# mcat-4cu-b-v2b.net
KiCad netlist of a schematic drawn in EAGLE
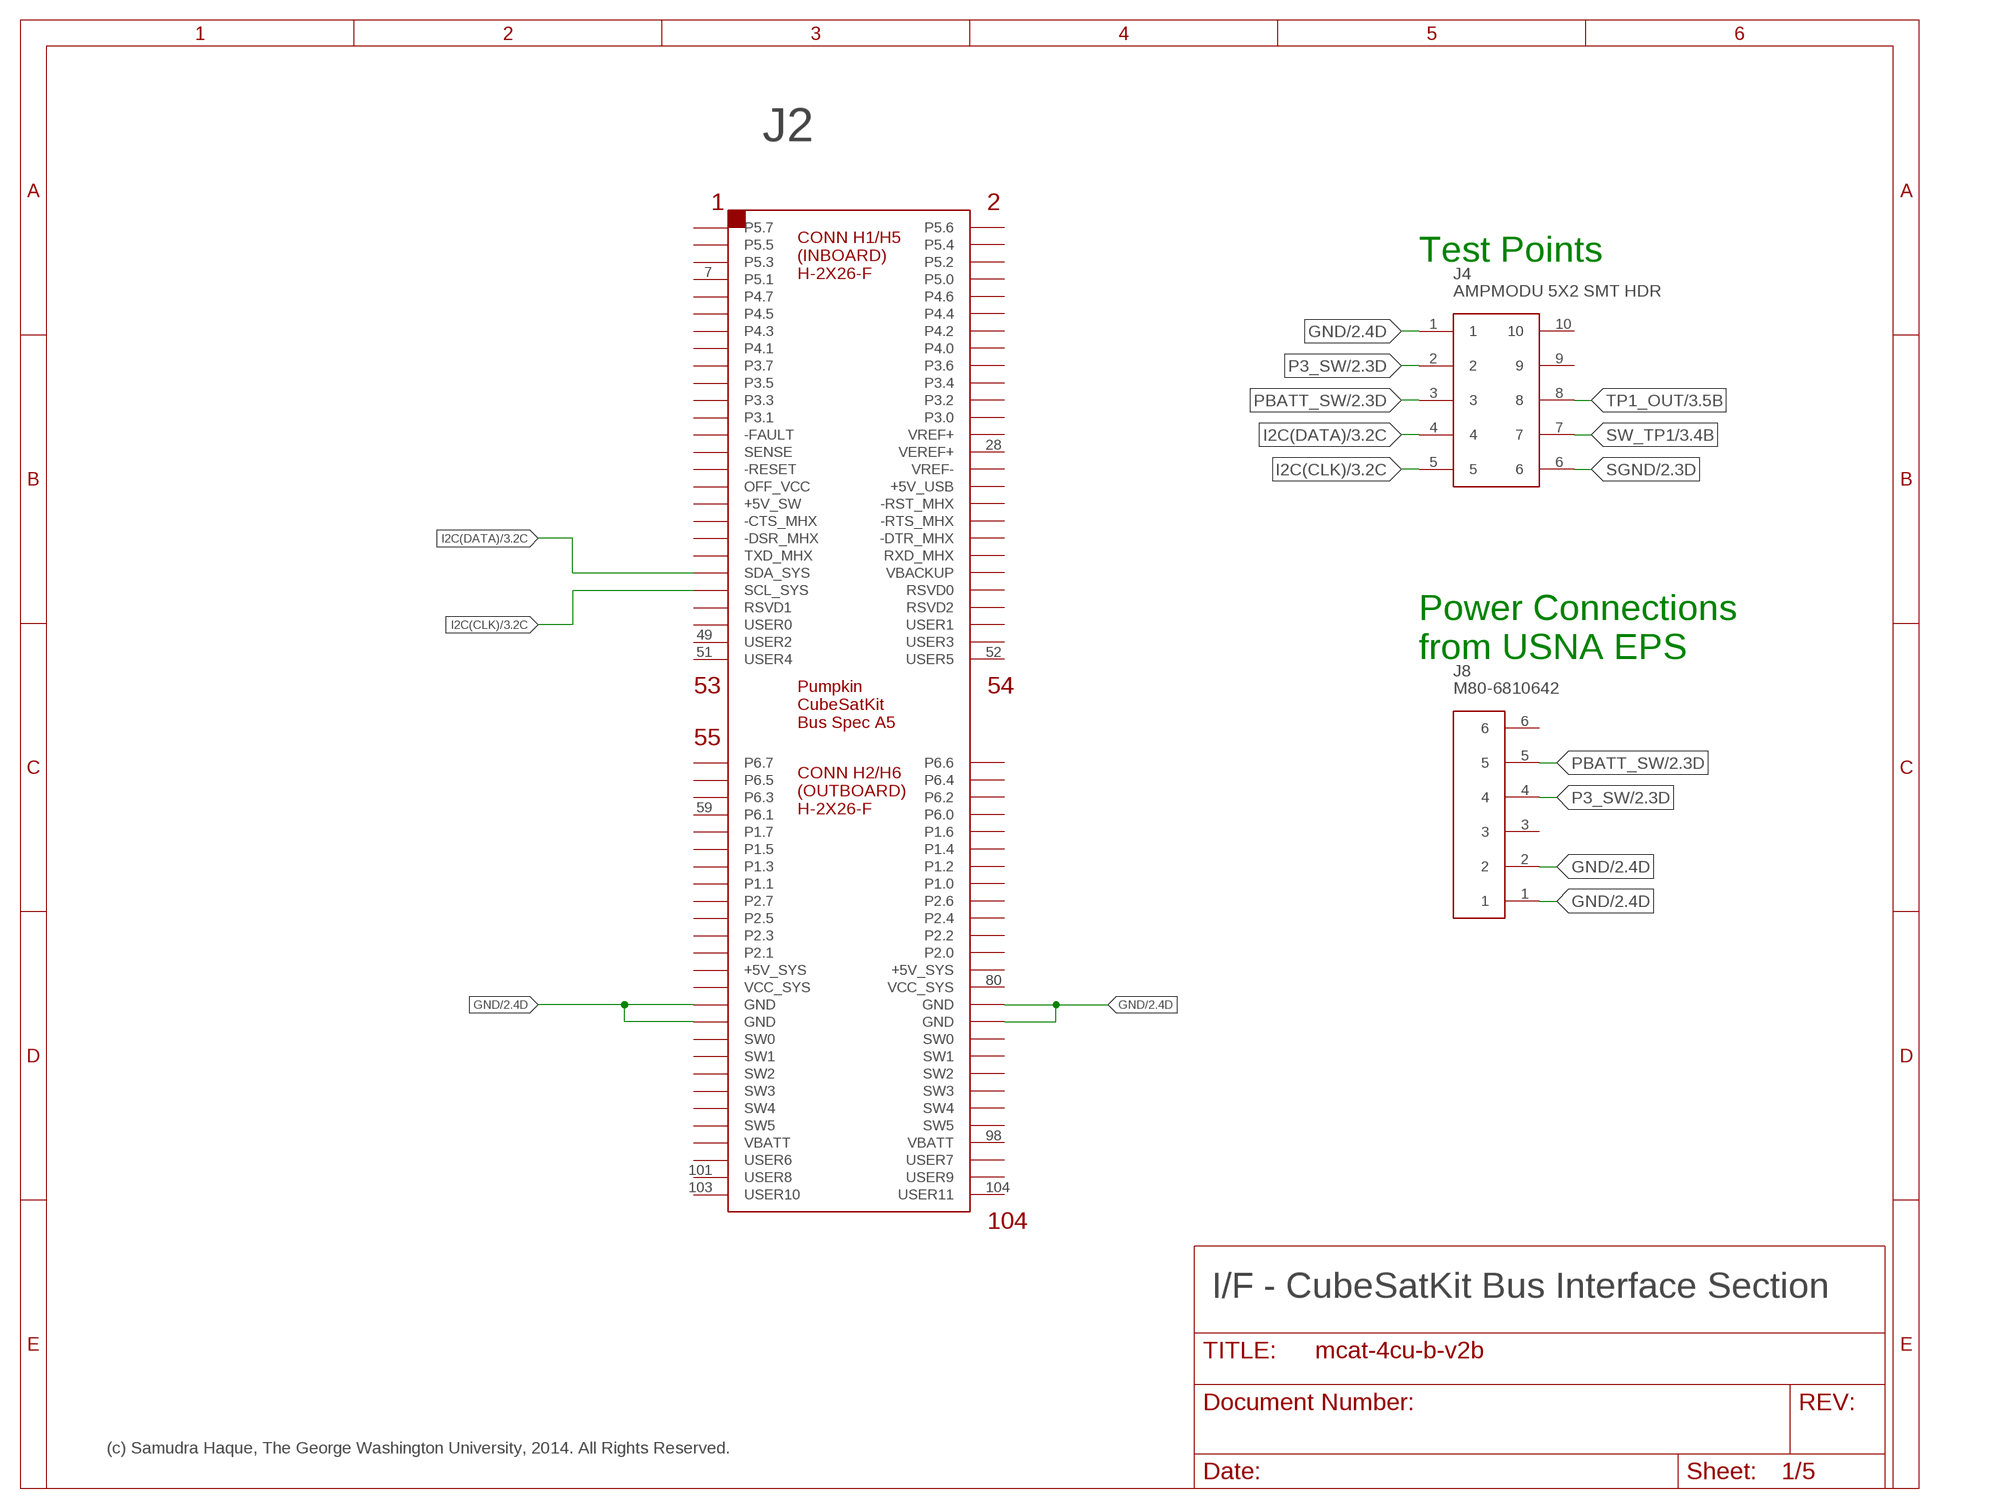
[diagram p0: schematic, sheet 1]
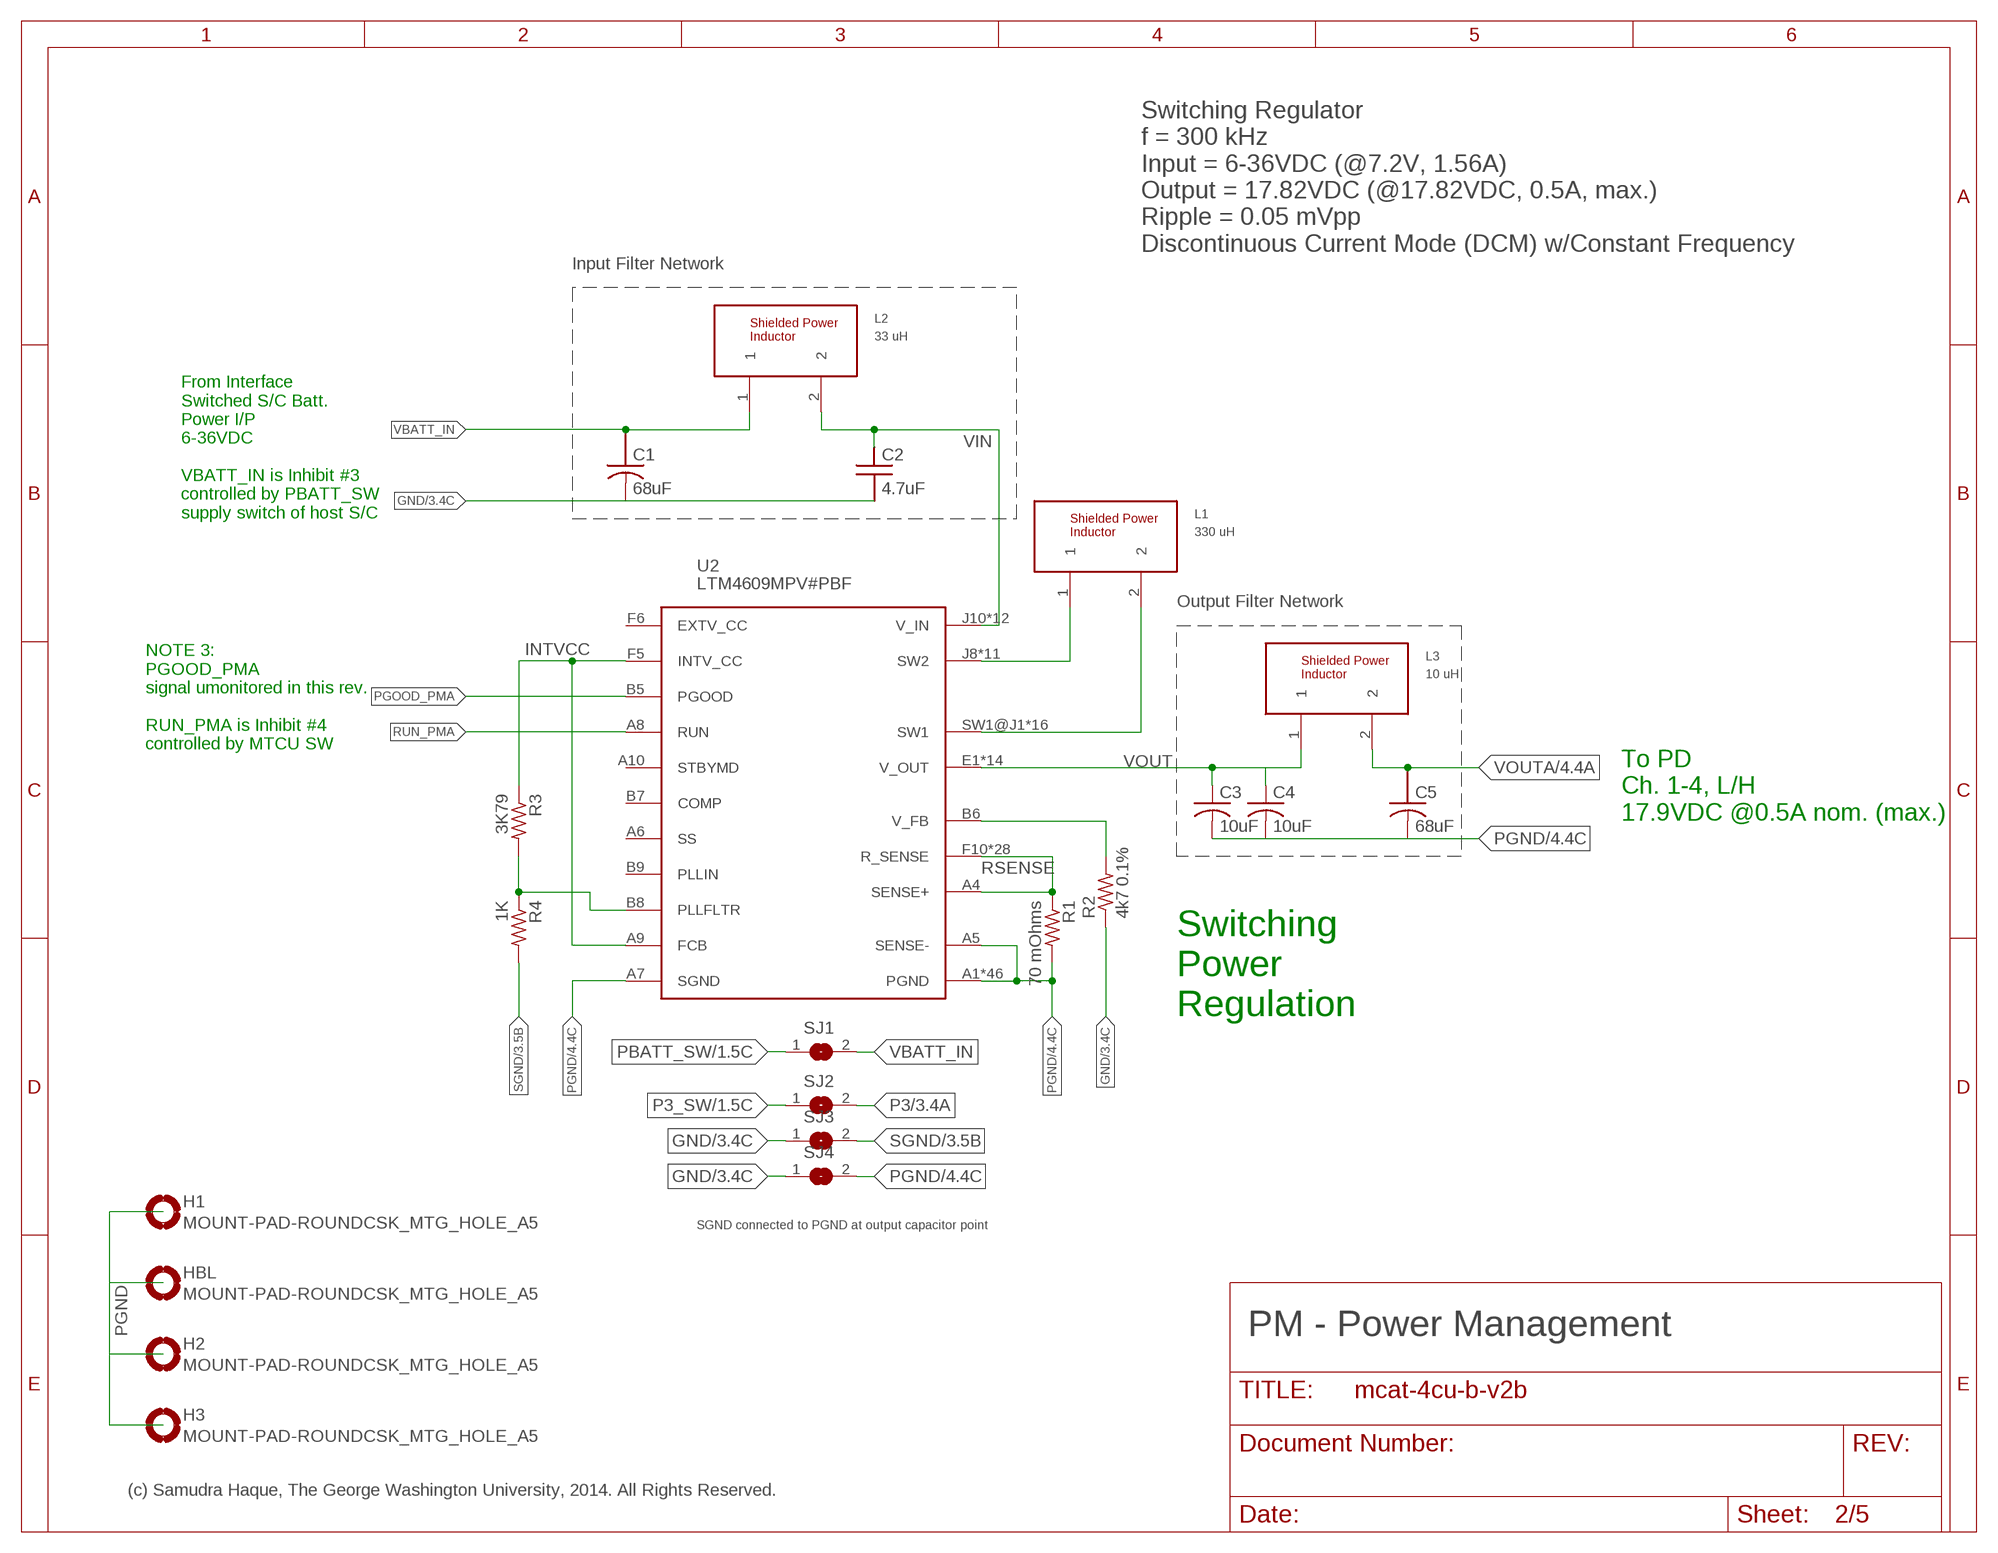
[diagram p1: schematic, sheet 2]
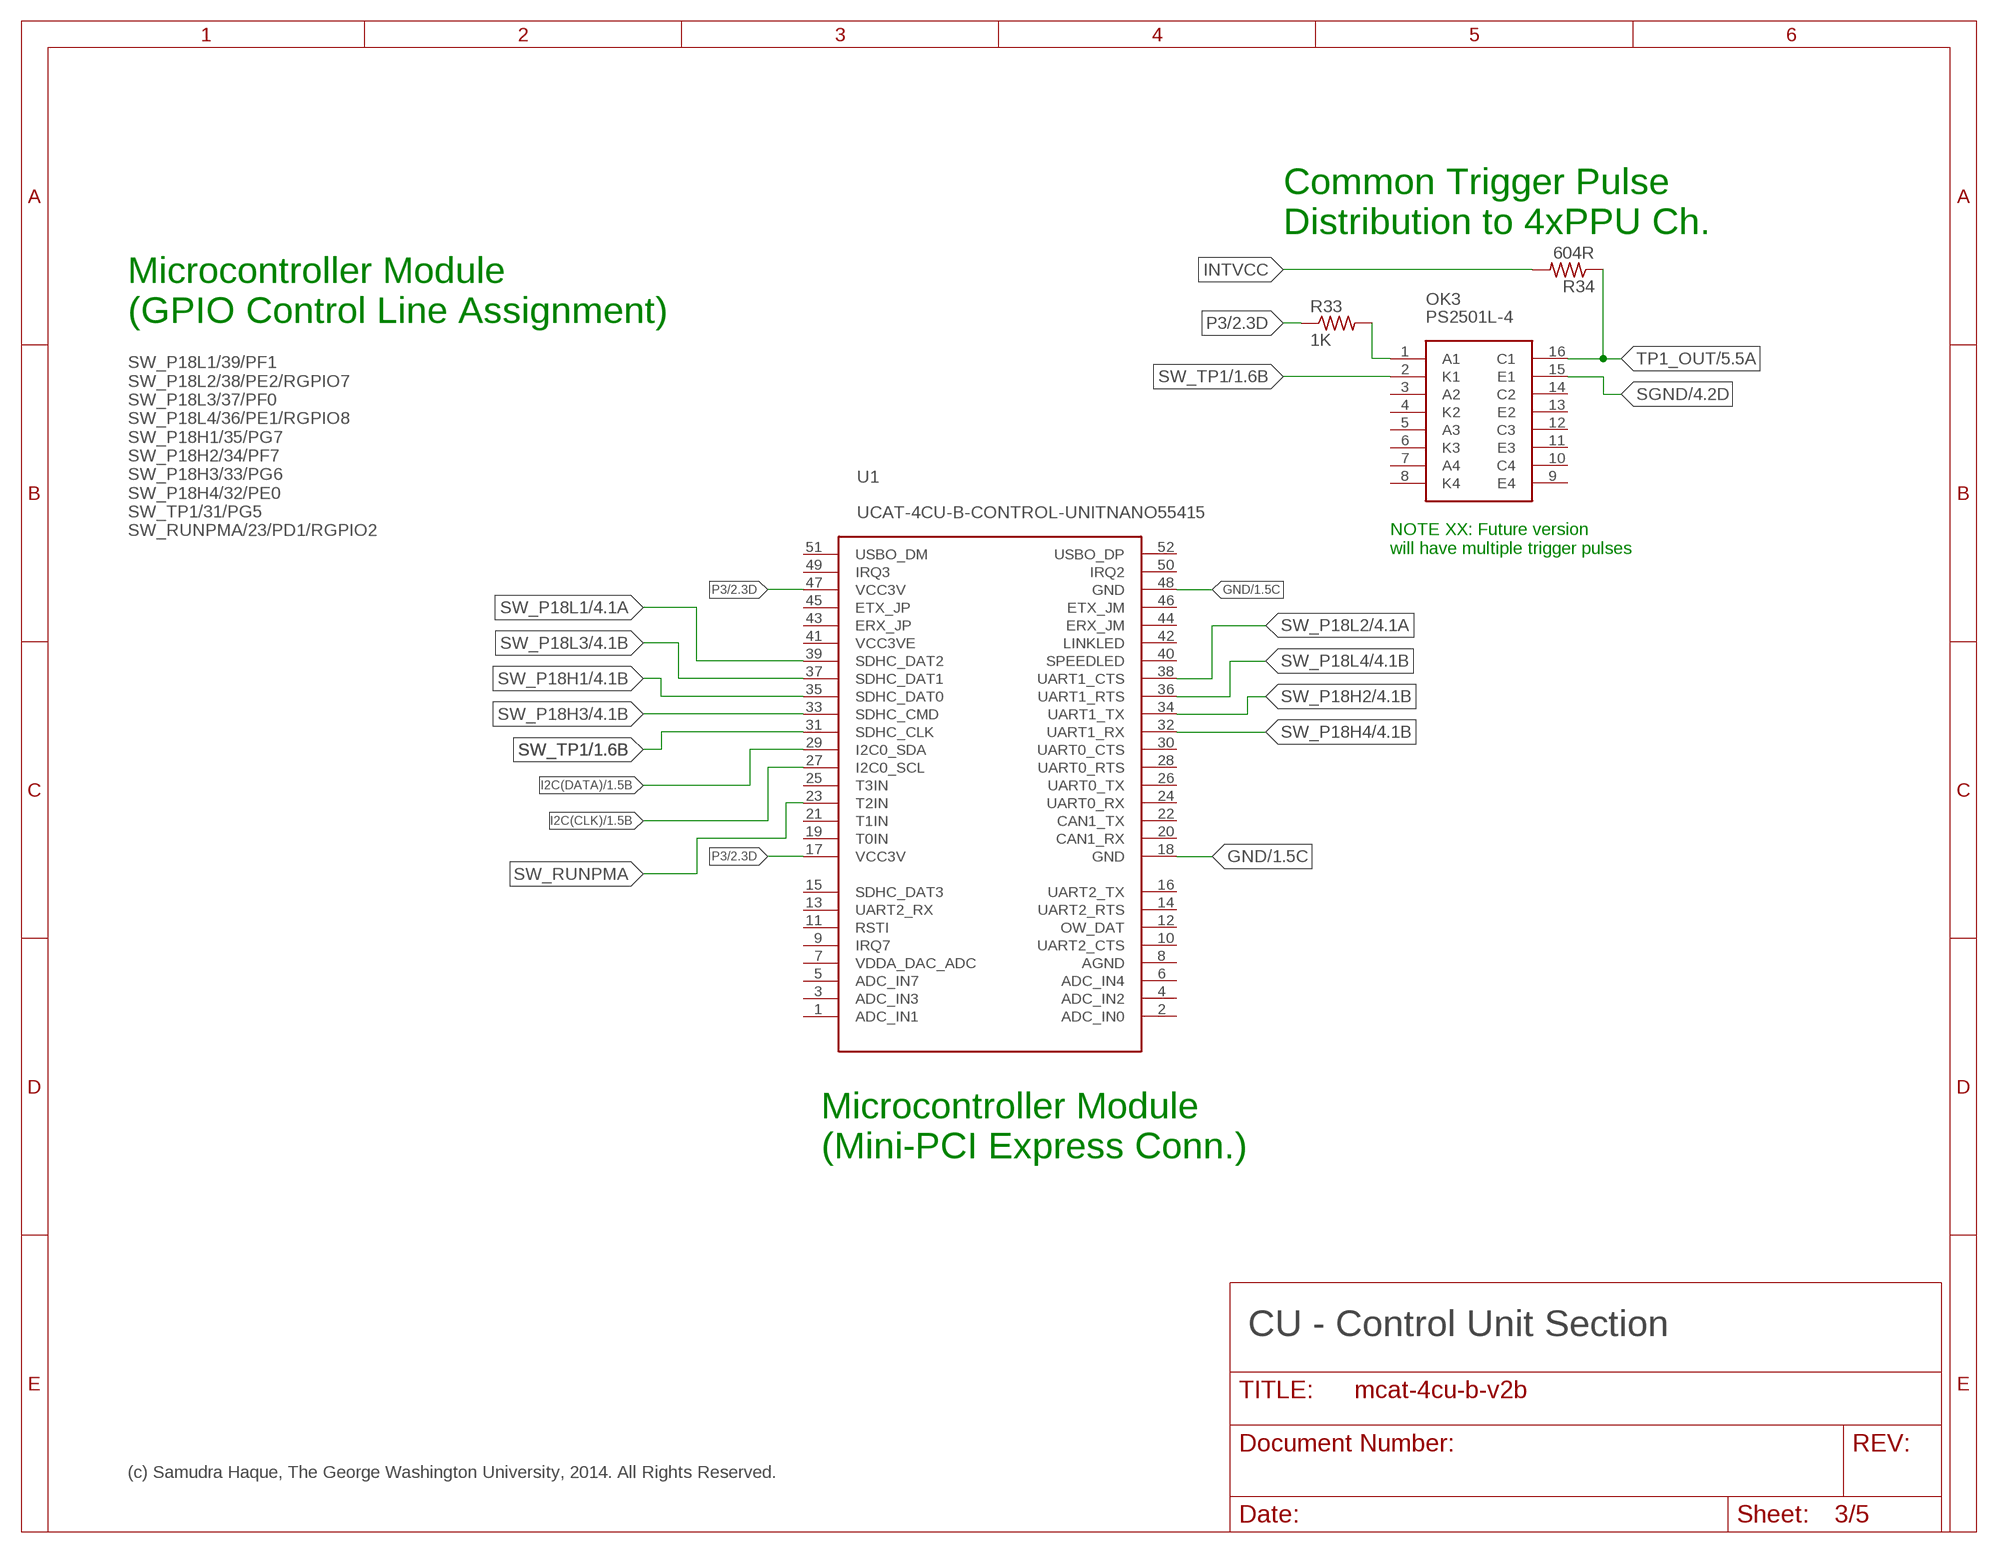
[diagram p2: schematic, sheet 3]
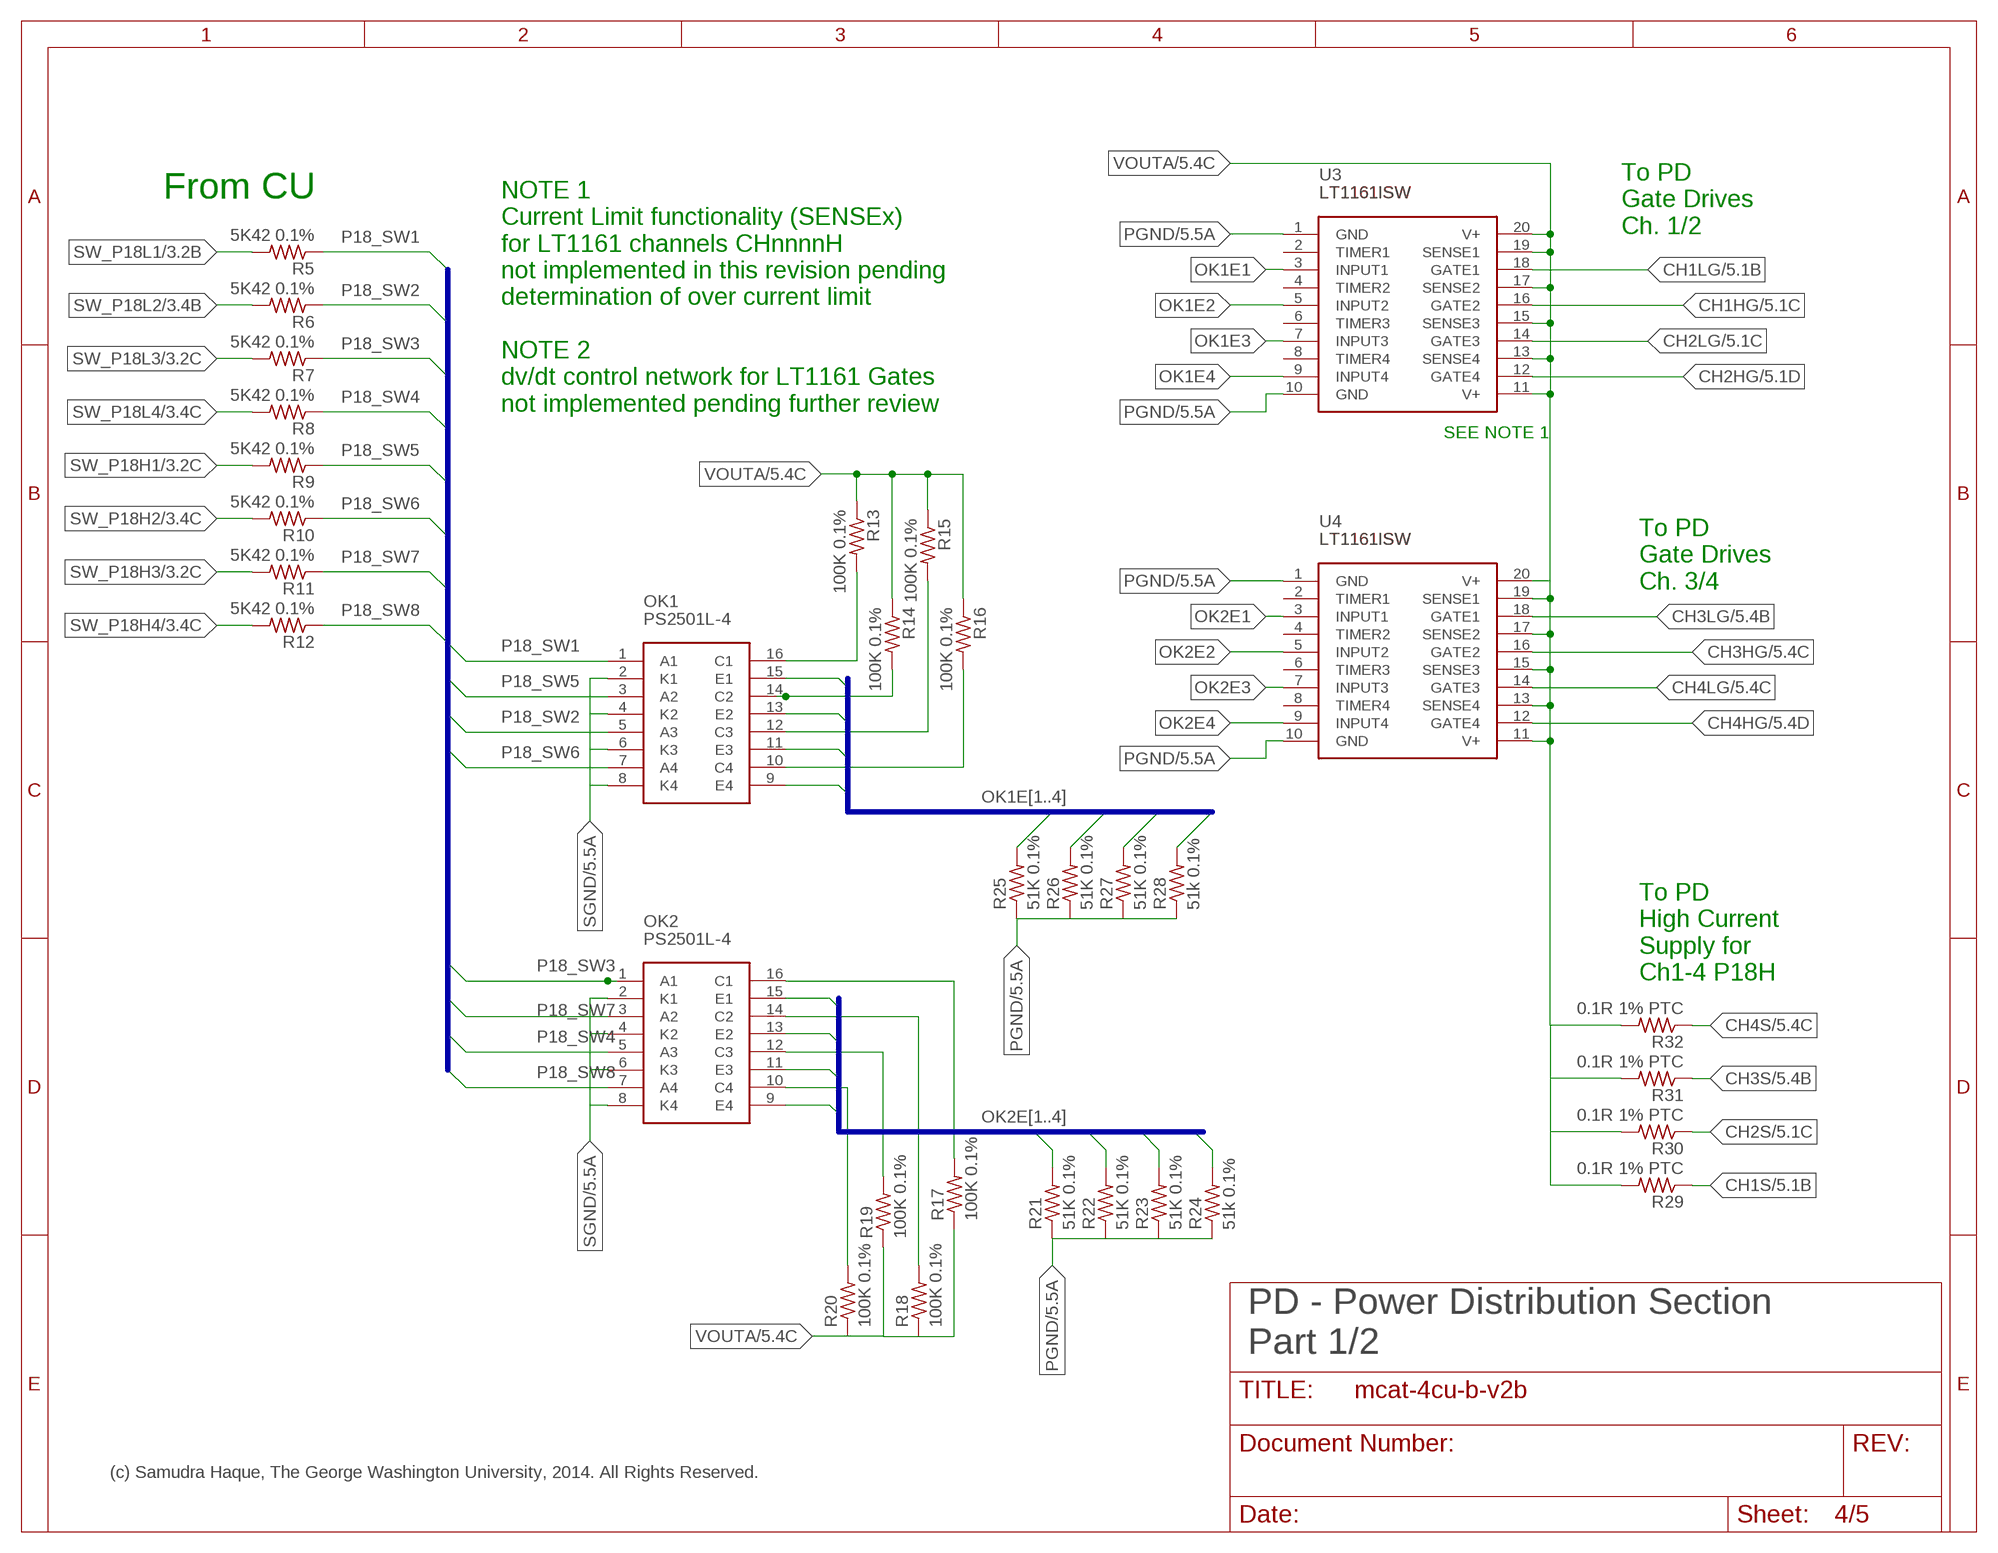
[diagram p3: schematic, sheet 4]
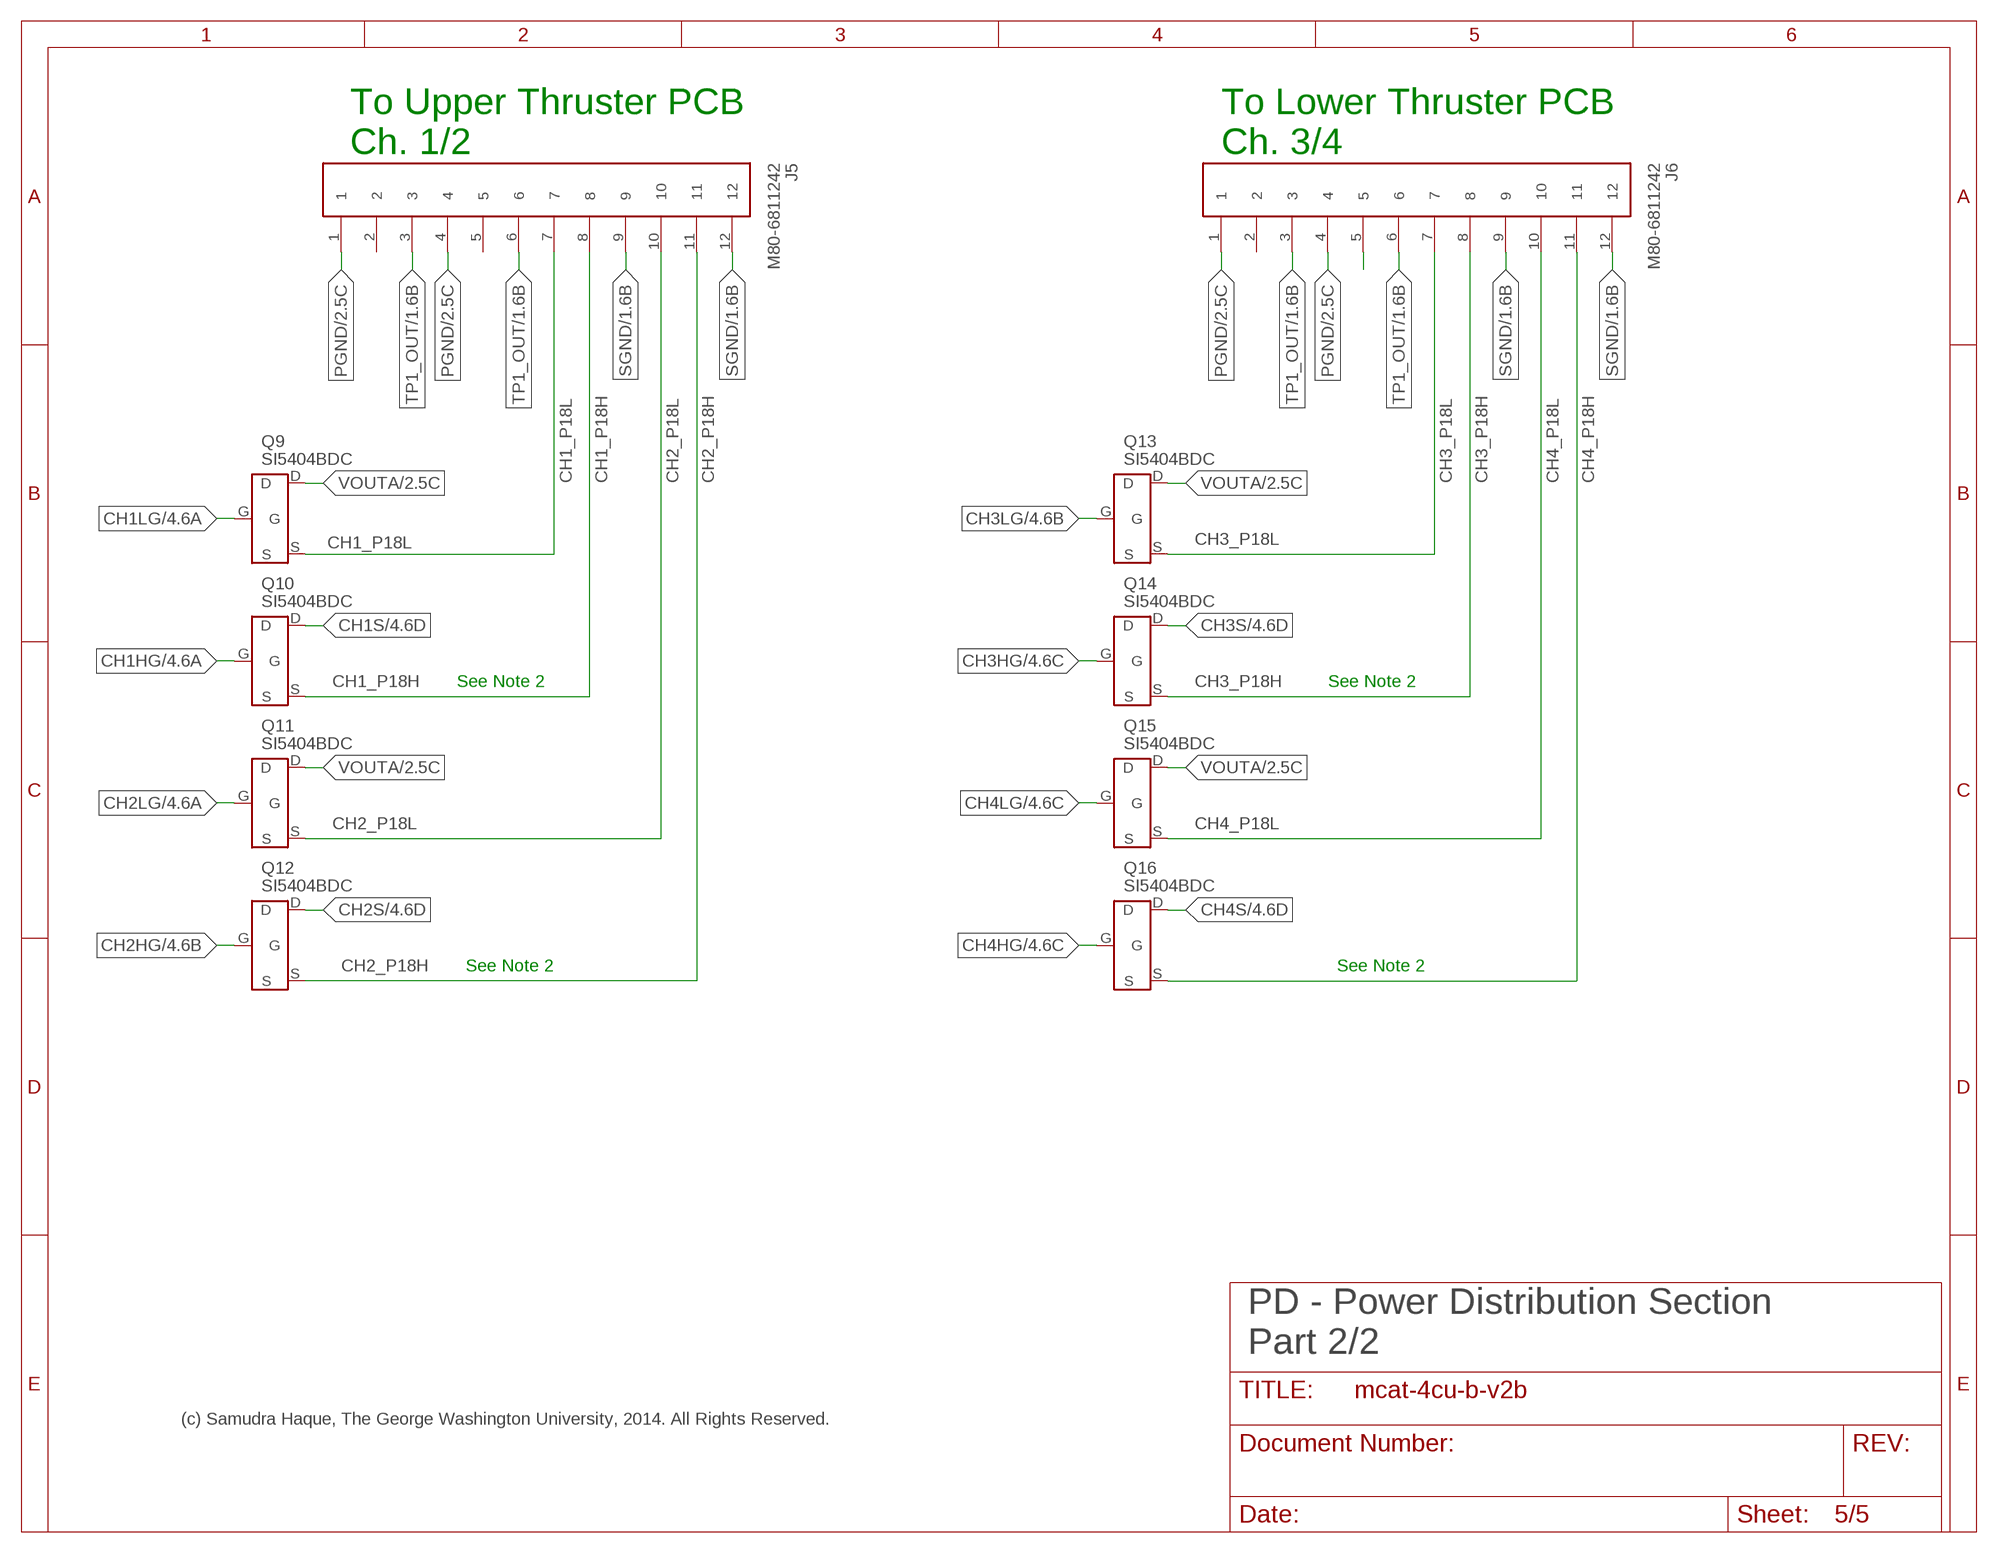
[diagram p4: schematic, sheet 5]

(export (version "E")
  (design (tool "Eeschema 10.0.6"))
  (components
    (comp (ref "OK1")
      (value "PS2501L-4")
      (footprint "eagle-import:PS2501L-4")
      (libsource (lib "eagle-import") (part "PS2501L-4"))
    )
    (comp (ref "OK2")
      (value "PS2501L-4")
      (footprint "eagle-import:PS2501L-4")
      (libsource (lib "eagle-import") (part "PS2501L-4"))
    )
    (comp (ref "R5")
      (value "5K42 0.1%")
      (footprint "eagle-import:R1206")
      (libsource (lib "eagle-import") (part "resistor_R-US_R1206"))
    )
    (comp (ref "R6")
      (value "5K42 0.1%")
      (footprint "eagle-import:R1206")
      (libsource (lib "eagle-import") (part "resistor_R-US_R1206"))
    )
    (comp (ref "R7")
      (value "5K42 0.1%")
      (footprint "eagle-import:R1206")
      (libsource (lib "eagle-import") (part "resistor_R-US_R1206"))
    )
    (comp (ref "R8")
      (value "5K42 0.1%")
      (footprint "eagle-import:R1206")
      (libsource (lib "eagle-import") (part "resistor_R-US_R1206"))
    )
    (comp (ref "R9")
      (value "5K42 0.1%")
      (footprint "eagle-import:R1206")
      (libsource (lib "eagle-import") (part "resistor_R-US_R1206"))
    )
    (comp (ref "R10")
      (value "5K42 0.1%")
      (footprint "eagle-import:R1206")
      (libsource (lib "eagle-import") (part "resistor_R-US_R1206"))
    )
    (comp (ref "R11")
      (value "5K42 0.1%")
      (footprint "eagle-import:R1206")
      (libsource (lib "eagle-import") (part "resistor_R-US_R1206"))
    )
    (comp (ref "R12")
      (value "5K42 0.1%")
      (footprint "eagle-import:R1206")
      (libsource (lib "eagle-import") (part "resistor_R-US_R1206"))
    )
    (comp (ref "R13")
      (value "100K 0.1%")
      (footprint "eagle-import:R0402")
      (libsource (lib "eagle-import") (part "resistor_R-US_R0402"))
    )
    (comp (ref "R14")
      (value "100K 0.1%")
      (footprint "eagle-import:R0402")
      (libsource (lib "eagle-import") (part "resistor_R-US_R0402"))
    )
    (comp (ref "R15")
      (value "100K 0.1%")
      (footprint "eagle-import:R0402")
      (libsource (lib "eagle-import") (part "resistor_R-US_R0402"))
    )
    (comp (ref "R16")
      (value "100K 0.1%")
      (footprint "eagle-import:R0402")
      (libsource (lib "eagle-import") (part "resistor_R-US_R0402"))
    )
    (comp (ref "R17")
      (value "100K 0.1%")
      (footprint "eagle-import:R0402")
      (libsource (lib "eagle-import") (part "resistor_R-US_R0402"))
    )
    (comp (ref "R18")
      (value "100K 0.1%")
      (footprint "eagle-import:R0402")
      (libsource (lib "eagle-import") (part "resistor_R-US_R0402"))
    )
    (comp (ref "R19")
      (value "100K 0.1%")
      (footprint "eagle-import:R0402")
      (libsource (lib "eagle-import") (part "resistor_R-US_R0402"))
    )
    (comp (ref "R20")
      (value "100K 0.1%")
      (footprint "eagle-import:R0402")
      (libsource (lib "eagle-import") (part "resistor_R-US_R0402"))
    )
    (comp (ref "R21")
      (value "51K 0.1%")
      (footprint "eagle-import:R0603")
      (libsource (lib "eagle-import") (part "resistor_R-US_R0603"))
    )
    (comp (ref "R22")
      (value "51K 0.1%")
      (footprint "eagle-import:R0603")
      (libsource (lib "eagle-import") (part "resistor_R-US_R0603"))
    )
    (comp (ref "R23")
      (value "51K 0.1%")
      (footprint "eagle-import:R0603")
      (libsource (lib "eagle-import") (part "resistor_R-US_R0603"))
    )
    (comp (ref "R24")
      (value "51k 0.1%")
      (footprint "eagle-import:R0603")
      (libsource (lib "eagle-import") (part "resistor_R-US_R0603"))
    )
    (comp (ref "R25")
      (value "51K 0.1%")
      (footprint "eagle-import:R0603")
      (libsource (lib "eagle-import") (part "resistor_R-US_R0603"))
    )
    (comp (ref "R26")
      (value "51K 0.1%")
      (footprint "eagle-import:R0603")
      (libsource (lib "eagle-import") (part "resistor_R-US_R0603"))
    )
    (comp (ref "R27")
      (value "51K 0.1%")
      (footprint "eagle-import:R0603")
      (libsource (lib "eagle-import") (part "resistor_R-US_R0603"))
    )
    (comp (ref "R28")
      (value "51k 0.1%")
      (footprint "eagle-import:R0603")
      (libsource (lib "eagle-import") (part "resistor_R-US_R0603"))
    )
    (comp (ref "R29")
      (value "0.1R 1% PTC")
      (footprint "eagle-import:R0402")
      (libsource (lib "eagle-import") (part "R-US_R0402"))
    )
    (comp (ref "R30")
      (value "0.1R 1% PTC")
      (footprint "eagle-import:R0402")
      (libsource (lib "eagle-import") (part "R-US_R0402"))
    )
    (comp (ref "R31")
      (value "0.1R 1% PTC")
      (footprint "eagle-import:R0402")
      (libsource (lib "eagle-import") (part "R-US_R0402"))
    )
    (comp (ref "R32")
      (value "0.1R 1% PTC")
      (footprint "eagle-import:R0402")
      (libsource (lib "eagle-import") (part "R-US_R0402"))
    )
    (comp (ref "U3")
      (value "LT1161ISW")
      (footprint "eagle-import:20-LEAD-PLASTIC-SO")
      (libsource (lib "eagle-import") (part "LT1161ISW"))
    )
    (comp (ref "U4")
      (value "LT1161ISW")
      (footprint "eagle-import:20-LEAD-PLASTIC-SO")
      (libsource (lib "eagle-import") (part "LT1161ISW"))
    )
    (comp (ref "OK3")
      (value "PS2501L-4")
      (footprint "eagle-import:PS2501L-4")
      (libsource (lib "eagle-import") (part "PS2501L-4"))
    )
    (comp (ref "R33")
      (value "1K")
      (footprint "eagle-import:R0805")
      (libsource (lib "eagle-import") (part "resistor_R-US_R0805"))
    )
    (comp (ref "R34")
      (value "604R")
      (footprint "eagle-import:R0805")
      (libsource (lib "eagle-import") (part "resistor_R-US_R0805"))
    )
    (comp (ref "U1")
      (value "UCAT-4CU-B-CONTROL-UNITNANO55415")
      (footprint "eagle-import:MOLEX-MINI-PCI-EXPRESS-8MM-52CKT")
      (libsource (lib "eagle-import") (part "UCAT-4CU-B-CONTROL-UNITNANO55415"))
    )
    (comp (ref "C1")
      (value "68uF")
      (footprint "eagle-import:OS-CON-SVPF-F12")
      (libsource (lib "eagle-import") (part "OSCON-50SVPF68M"))
    )
    (comp (ref "C2")
      (value "4.7uF")
      (footprint "eagle-import:MLCC-X7R-1210")
      (libsource (lib "eagle-import") (part "AVX-LD105C475KAB2A"))
    )
    (comp (ref "C3")
      (value "10uF")
      (footprint "eagle-import:C1210K")
      (libsource (lib "eagle-import") (part "C-USC1210K"))
    )
    (comp (ref "C4")
      (value "10uF")
      (footprint "eagle-import:C1210K")
      (libsource (lib "eagle-import") (part "C-USC1210K"))
    )
    (comp (ref "C5")
      (value "68uF")
      (footprint "eagle-import:OS-CON-SVPF-F12")
      (libsource (lib "eagle-import") (part "OSCON-50SVPF68M"))
    )
    (comp (ref "H1")
      (value "MOUNT-PAD-ROUNDCSK_MTG_HOLE_A5")
      (footprint "eagle-import:CSK_MOUNTING_HOLE")
      (libsource (lib "eagle-import") (part "MOUNT-PAD-ROUNDCSK_MTG_HOLE_A5"))
    )
    (comp (ref "H2")
      (value "MOUNT-PAD-ROUNDCSK_MTG_HOLE_A5")
      (footprint "eagle-import:CSK_MOUNTING_HOLE")
      (libsource (lib "eagle-import") (part "MOUNT-PAD-ROUNDCSK_MTG_HOLE_A5"))
    )
    (comp (ref "H3")
      (value "MOUNT-PAD-ROUNDCSK_MTG_HOLE_A5")
      (footprint "eagle-import:CSK_MOUNTING_HOLE")
      (libsource (lib "eagle-import") (part "MOUNT-PAD-ROUNDCSK_MTG_HOLE_A5"))
    )
    (comp (ref "HBL")
      (value "MOUNT-PAD-ROUNDCSK_MTG_HOLE_A5")
      (footprint "eagle-import:CSK_MOUNTING_HOLE")
      (libsource (lib "eagle-import") (part "MOUNT-PAD-ROUNDCSK_MTG_HOLE_A5"))
    )
    (comp (ref "L1")
      (value "330 uH")
      (footprint "eagle-import:MSS1048")
      (libsource (lib "eagle-import") (part "MSS1048-334KL_"))
    )
    (comp (ref "L2")
      (value "33 uH")
      (footprint "eagle-import:MSS1048")
      (libsource (lib "eagle-import") (part "MSS1038-333ML_"))
    )
    (comp (ref "L3")
      (value "10 uH")
      (footprint "eagle-import:SERIES-POWER-INDUCTORS")
      (fields (field (name "MF") "PANASONIC") (field (name "MPN") "ELL5PS100M"))
      (libsource (lib "eagle-import") (part "ELL-5PS100M"))
    )
    (comp (ref "R1")
      (value "70 mOhms")
      (footprint "eagle-import:R1206")
      (libsource (lib "eagle-import") (part "resistor_R-US_R1206"))
    )
    (comp (ref "R2")
      (value "4k7 0.1%")
      (footprint "eagle-import:R0603")
      (libsource (lib "eagle-import") (part "resistor_R-US_R0603"))
    )
    (comp (ref "R3")
      (value "3K79")
      (footprint "eagle-import:R0805")
      (libsource (lib "eagle-import") (part "R-US_R0805"))
    )
    (comp (ref "R4")
      (value "1K")
      (footprint "eagle-import:R0805")
      (libsource (lib "eagle-import") (part "R-US_R0805"))
    )
    (comp (ref "SJ1") (value "SJ") (footprint "eagle-import:SJ") (libsource (lib "eagle-import") (part "SJ")))
    (comp (ref "SJ2") (value "SJ") (footprint "eagle-import:SJ") (libsource (lib "eagle-import") (part "SJ")))
    (comp (ref "SJ3") (value "SJ") (footprint "eagle-import:SJ") (libsource (lib "eagle-import") (part "SJ")))
    (comp (ref "SJ4") (value "SJ") (footprint "eagle-import:SJ") (libsource (lib "eagle-import") (part "SJ")))
    (comp (ref "U2")
      (value "LTM4609MPV#PBF")
      (footprint "eagle-import:LGA-141-LTC-05-08-1840-B")
      (libsource (lib "eagle-import") (part "LTM4609MPV#PBFROHS/HITEMP"))
    )
    (comp (ref "J2")
      (value "CSK-BUS-CONN2X2X26")
      (footprint "eagle-import:CSK-BUS-PKG")
      (libsource (lib "eagle-import") (part "CSK-BUS-CONN2X2X26"))
    )
    (comp (ref "J4")
      (value "AMPMODU 5X2 SMT HDR")
      (footprint "eagle-import:AMPMODU-SMT-PIN-HEADER-5X2")
      (libsource (lib "eagle-import") (part "AMPMODU-5-146131-X(5X2)"))
    )
    (comp (ref "J8")
      (value "M80-6810642")
      (footprint "eagle-import:M80-68106")
      (libsource (lib "eagle-import") (part "M80-6810642"))
    )
    (comp (ref "J5")
      (value "M80-6811242")
      (footprint "eagle-import:M80-68112")
      (libsource (lib "eagle-import") (part "M80-6811242"))
    )
    (comp (ref "J6")
      (value "M80-6811242")
      (footprint "eagle-import:M80-68112")
      (libsource (lib "eagle-import") (part "M80-6811242"))
    )
    (comp (ref "Q9")
      (value "SI5404BDC")
      (footprint "eagle-import:1206-8-CHIPFET")
      (libsource (lib "eagle-import") (part "SI5404BDC"))
    )
    (comp (ref "Q10")
      (value "SI5404BDC")
      (footprint "eagle-import:1206-8-CHIPFET")
      (libsource (lib "eagle-import") (part "SI5404BDC"))
    )
    (comp (ref "Q11")
      (value "SI5404BDC")
      (footprint "eagle-import:1206-8-CHIPFET")
      (libsource (lib "eagle-import") (part "SI5404BDC"))
    )
    (comp (ref "Q12")
      (value "SI5404BDC")
      (footprint "eagle-import:1206-8-CHIPFET")
      (libsource (lib "eagle-import") (part "SI5404BDC"))
    )
    (comp (ref "Q13")
      (value "SI5404BDC")
      (footprint "eagle-import:1206-8-CHIPFET")
      (libsource (lib "eagle-import") (part "SI5404BDC"))
    )
    (comp (ref "Q14")
      (value "SI5404BDC")
      (footprint "eagle-import:1206-8-CHIPFET")
      (libsource (lib "eagle-import") (part "SI5404BDC"))
    )
    (comp (ref "Q15")
      (value "SI5404BDC")
      (footprint "eagle-import:1206-8-CHIPFET")
      (libsource (lib "eagle-import") (part "SI5404BDC"))
    )
    (comp (ref "Q16")
      (value "SI5404BDC")
      (footprint "eagle-import:1206-8-CHIPFET")
      (libsource (lib "eagle-import") (part "SI5404BDC"))
    )
  )
  (nets
    (net (code "3") (name "CH1HG") (class "Default")
      (node (ref "Q10") (pin "G") (pinfunction "G_G") (pintype "bidirectional"))
      (node (ref "U3") (pin "16") (pinfunction "GATE2_16") (pintype "bidirectional"))
    )
    (net (code "4") (name "CH1LG") (class "Default")
      (node (ref "Q9") (pin "G") (pinfunction "G_G") (pintype "bidirectional"))
      (node (ref "U3") (pin "18") (pinfunction "GATE1_18") (pintype "bidirectional"))
    )
    (net (code "5") (name "CH1S") (class "Default")
      (node (ref "Q10") (pin "D") (pinfunction "D_D") (pintype "bidirectional"))
      (node (ref "R29") (pin "1") (pinfunction "1_1") (pintype "passive"))
    )
    (net (code "6") (name "CH1_P18H") (class "Default")
      (node (ref "J5") (pin "8") (pinfunction "8_8") (pintype "bidirectional"))
      (node (ref "Q10") (pin "S") (pinfunction "S_S") (pintype "bidirectional"))
    )
    (net (code "7") (name "CH1_P18L") (class "Default")
      (node (ref "J5") (pin "7") (pinfunction "7_7") (pintype "bidirectional"))
      (node (ref "Q9") (pin "S") (pinfunction "S_S") (pintype "bidirectional"))
    )
    (net (code "8") (name "CH2HG") (class "Default")
      (node (ref "Q12") (pin "G") (pinfunction "G_G") (pintype "bidirectional"))
      (node (ref "U3") (pin "12") (pinfunction "GATE4_12") (pintype "bidirectional"))
    )
    (net (code "9") (name "CH2LG") (class "Default")
      (node (ref "Q11") (pin "G") (pinfunction "G_G") (pintype "bidirectional"))
      (node (ref "U3") (pin "14") (pinfunction "GATE3_14") (pintype "bidirectional"))
    )
    (net (code "10") (name "CH2S") (class "Default")
      (node (ref "Q12") (pin "D") (pinfunction "D_D") (pintype "bidirectional"))
      (node (ref "R30") (pin "1") (pinfunction "1_1") (pintype "passive"))
    )
    (net (code "11") (name "CH2_P18H") (class "Default")
      (node (ref "J5") (pin "11") (pinfunction "11_11") (pintype "bidirectional"))
      (node (ref "Q12") (pin "S") (pinfunction "S_S") (pintype "bidirectional"))
    )
    (net (code "12") (name "CH2_P18L") (class "Default")
      (node (ref "J5") (pin "10") (pinfunction "10_10") (pintype "bidirectional"))
      (node (ref "Q11") (pin "S") (pinfunction "S_S") (pintype "bidirectional"))
    )
    (net (code "13") (name "CH3HG") (class "Default")
      (node (ref "Q14") (pin "G") (pinfunction "G_G") (pintype "bidirectional"))
      (node (ref "U4") (pin "16") (pinfunction "GATE2_16") (pintype "bidirectional"))
    )
    (net (code "14") (name "CH3LG") (class "Default")
      (node (ref "Q13") (pin "G") (pinfunction "G_G") (pintype "bidirectional"))
      (node (ref "U4") (pin "18") (pinfunction "GATE1_18") (pintype "bidirectional"))
    )
    (net (code "15") (name "CH3S") (class "Default")
      (node (ref "Q14") (pin "D") (pinfunction "D_D") (pintype "bidirectional"))
      (node (ref "R31") (pin "1") (pinfunction "1_1") (pintype "passive"))
    )
    (net (code "16") (name "CH3_P18H") (class "Default")
      (node (ref "J6") (pin "8") (pinfunction "8_8") (pintype "bidirectional"))
      (node (ref "Q14") (pin "S") (pinfunction "S_S") (pintype "bidirectional"))
    )
    (net (code "17") (name "CH3_P18L") (class "Default")
      (node (ref "J6") (pin "7") (pinfunction "7_7") (pintype "bidirectional"))
      (node (ref "Q13") (pin "S") (pinfunction "S_S") (pintype "bidirectional"))
    )
    (net (code "18") (name "CH4HG") (class "Default")
      (node (ref "Q16") (pin "G") (pinfunction "G_G") (pintype "bidirectional"))
      (node (ref "U4") (pin "12") (pinfunction "GATE4_12") (pintype "bidirectional"))
    )
    (net (code "19") (name "CH4LG") (class "Default")
      (node (ref "Q15") (pin "G") (pinfunction "G_G") (pintype "bidirectional"))
      (node (ref "U4") (pin "14") (pinfunction "GATE3_14") (pintype "bidirectional"))
    )
    (net (code "20") (name "CH4S") (class "Default")
      (node (ref "Q16") (pin "D") (pinfunction "D_D") (pintype "bidirectional"))
      (node (ref "R32") (pin "1") (pinfunction "1_1") (pintype "passive"))
    )
    (net (code "21") (name "CH4_P18H") (class "Default")
      (node (ref "J6") (pin "11") (pinfunction "11_11") (pintype "bidirectional"))
      (node (ref "Q16") (pin "S") (pinfunction "S_S") (pintype "bidirectional"))
    )
    (net (code "22") (name "CH4_P18L") (class "Default")
      (node (ref "J6") (pin "10") (pinfunction "10_10") (pintype "bidirectional"))
      (node (ref "Q15") (pin "S") (pinfunction "S_S") (pintype "bidirectional"))
    )
    (net (code "23") (name "GND") (class "Default")
      (node (ref "C1") (pin "K1") (pinfunction "K_K1") (pintype "passive"))
      (node (ref "C2") (pin "2") (pinfunction "2_2") (pintype "passive"))
      (node (ref "J2") (pin "81") (pinfunction "GND_81") (pintype "bidirectional"))
      (node (ref "J2") (pin "82") (pinfunction "GND_82") (pintype "bidirectional"))
      (node (ref "J2") (pin "83") (pinfunction "GND_83") (pintype "bidirectional"))
      (node (ref "J2") (pin "84") (pinfunction "GND_84") (pintype "bidirectional"))
      (node (ref "J4") (pin "1") (pinfunction "1_1") (pintype "bidirectional"))
      (node (ref "J8") (pin "1") (pinfunction "1_1") (pintype "bidirectional"))
      (node (ref "J8") (pin "2") (pinfunction "2_2") (pintype "bidirectional"))
      (node (ref "R2") (pin "1") (pinfunction "1_1") (pintype "passive"))
      (node (ref "SJ3") (pin "1") (pinfunction "1_1") (pintype "passive"))
      (node (ref "SJ4") (pin "1") (pinfunction "1_1") (pintype "passive"))
      (node (ref "U1") (pin "18") (pinfunction "GND_18") (pintype "bidirectional"))
      (node (ref "U1") (pin "48") (pinfunction "GND_48") (pintype "bidirectional"))
    )
    (net (code "24") (name "I2C(CLK)") (class "Default")
      (node (ref "J2") (pin "43") (pinfunction "SCL_SYS_43") (pintype "bidirectional"))
      (node (ref "J4") (pin "5") (pinfunction "5_5") (pintype "bidirectional"))
      (node (ref "U1") (pin "27") (pinfunction "I2C0_SCL_27") (pintype "bidirectional"))
    )
    (net (code "25") (name "I2C(DATA)") (class "Default")
      (node (ref "J2") (pin "41") (pinfunction "SDA_SYS_41") (pintype "bidirectional"))
      (node (ref "J4") (pin "4") (pinfunction "4_4") (pintype "bidirectional"))
      (node (ref "U1") (pin "29") (pinfunction "I2C0_SDA_29") (pintype "bidirectional"))
    )
    (net (code "26") (name "INTVCC") (class "Default")
      (node (ref "R3") (pin "1") (pinfunction "1_1") (pintype "passive"))
      (node (ref "R34") (pin "2") (pinfunction "2_2") (pintype "passive"))
      (node (ref "U2") (pin "A9") (pinfunction "FCB_A9") (pintype "bidirectional"))
      (node (ref "U2") (pin "F5") (pinfunction "INTV_CC_F5") (pintype "bidirectional"))
    )
    (net (code "27") (name "Net-(L1-Pad1)") (class "Default")
      (node (ref "L1") (pin "1") (pinfunction "1_1") (pintype "bidirectional"))
      (node (ref "U2") (pin "J8") (pinfunction "SW2_J8") (pintype "bidirectional"))
      (node (ref "U2") (pin "J9") (pinfunction "SW2_J9") (pintype "bidirectional"))
      (node (ref "U2") (pin "K7") (pinfunction "SW2_K7") (pintype "bidirectional"))
      (node (ref "U2") (pin "K8") (pinfunction "SW2_K8") (pintype "bidirectional"))
      (node (ref "U2") (pin "K9") (pinfunction "SW2_K9") (pintype "bidirectional"))
      (node (ref "U2") (pin "L7") (pinfunction "SW2_L7") (pintype "bidirectional"))
      (node (ref "U2") (pin "L8") (pinfunction "SW2_L8") (pintype "bidirectional"))
      (node (ref "U2") (pin "L9") (pinfunction "SW2_L9") (pintype "bidirectional"))
      (node (ref "U2") (pin "M7") (pinfunction "SW2_M7") (pintype "bidirectional"))
      (node (ref "U2") (pin "M8") (pinfunction "SW2_M8") (pintype "bidirectional"))
      (node (ref "U2") (pin "M9") (pinfunction "SW2_M9") (pintype "bidirectional"))
    )
    (net (code "28") (name "Net-(L1-Pad2)") (class "Default")
      (node (ref "L1") (pin "2") (pinfunction "2_2") (pintype "bidirectional"))
      (node (ref "U2") (pin "SW1@J1") (pinfunction "SW1_SW1@J1") (pintype "bidirectional"))
      (node (ref "U2") (pin "SW1@J2") (pinfunction "SW1_SW1@J2") (pintype "bidirectional"))
      (node (ref "U2") (pin "SW1@J3") (pinfunction "SW1_SW1@J3") (pintype "bidirectional"))
      (node (ref "U2") (pin "SW1@J4") (pinfunction "SW1_SW1@J4") (pintype "bidirectional"))
      (node (ref "U2") (pin "SW1@K1") (pinfunction "SW1_SW1@K1") (pintype "bidirectional"))
      (node (ref "U2") (pin "SW1@K2") (pinfunction "SW1_SW1@K2") (pintype "bidirectional"))
      (node (ref "U2") (pin "SW1@K3") (pinfunction "SW1_SW1@K3") (pintype "bidirectional"))
      (node (ref "U2") (pin "SW1@K4") (pinfunction "SW1_SW1@K4") (pintype "bidirectional"))
      (node (ref "U2") (pin "SW1@L1") (pinfunction "SW1_SW1@L1") (pintype "bidirectional"))
      (node (ref "U2") (pin "SW1@L2") (pinfunction "SW1_SW1@L2") (pintype "bidirectional"))
      (node (ref "U2") (pin "SW1@L3") (pinfunction "SW1_SW1@L3") (pintype "bidirectional"))
      (node (ref "U2") (pin "SW1@L4") (pinfunction "SW1_SW1@L4") (pintype "bidirectional"))
      (node (ref "U2") (pin "SW1@M1") (pinfunction "SW1_SW1@M1") (pintype "bidirectional"))
      (node (ref "U2") (pin "SW1@M2") (pinfunction "SW1_SW1@M2") (pintype "bidirectional"))
      (node (ref "U2") (pin "SW1@M3") (pinfunction "SW1_SW1@M3") (pintype "bidirectional"))
      (node (ref "U2") (pin "SW1@M4") (pinfunction "SW1_SW1@M4") (pintype "bidirectional"))
    )
    (net (code "29") (name "Net-(OK1-C1)") (class "Default")
      (node (ref "OK1") (pin "16") (pinfunction "C1_16") (pintype "bidirectional"))
      (node (ref "R13") (pin "2") (pinfunction "2_2") (pintype "passive"))
    )
    (net (code "30") (name "Net-(OK1-C2)") (class "Default")
      (node (ref "OK1") (pin "14") (pinfunction "C2_14") (pintype "bidirectional"))
      (node (ref "R14") (pin "2") (pinfunction "2_2") (pintype "passive"))
    )
    (net (code "31") (name "Net-(OK1-C3)") (class "Default")
      (node (ref "OK1") (pin "12") (pinfunction "C3_12") (pintype "bidirectional"))
      (node (ref "R15") (pin "2") (pinfunction "2_2") (pintype "passive"))
    )
    (net (code "32") (name "Net-(OK1-C4)") (class "Default")
      (node (ref "OK1") (pin "10") (pinfunction "C4_10") (pintype "bidirectional"))
      (node (ref "R16") (pin "2") (pinfunction "2_2") (pintype "passive"))
    )
    (net (code "33") (name "Net-(OK2-C1)") (class "Default")
      (node (ref "OK2") (pin "16") (pinfunction "C1_16") (pintype "bidirectional"))
      (node (ref "R17") (pin "2") (pinfunction "2_2") (pintype "passive"))
    )
    (net (code "34") (name "Net-(OK2-C2)") (class "Default")
      (node (ref "OK2") (pin "14") (pinfunction "C2_14") (pintype "bidirectional"))
      (node (ref "R18") (pin "2") (pinfunction "2_2") (pintype "passive"))
    )
    (net (code "35") (name "Net-(OK2-C3)") (class "Default")
      (node (ref "OK2") (pin "12") (pinfunction "C3_12") (pintype "bidirectional"))
      (node (ref "R19") (pin "2") (pinfunction "2_2") (pintype "passive"))
    )
    (net (code "36") (name "Net-(OK2-C4)") (class "Default")
      (node (ref "OK2") (pin "10") (pinfunction "C4_10") (pintype "bidirectional"))
      (node (ref "R20") (pin "2") (pinfunction "2_2") (pintype "passive"))
    )
    (net (code "37") (name "Net-(OK3-A1)") (class "Default")
      (node (ref "OK3") (pin "1") (pinfunction "A1_1") (pintype "bidirectional"))
      (node (ref "R33") (pin "2") (pinfunction "2_2") (pintype "passive"))
    )
    (net (code "38") (name "Net-(U2-PLLFLTR)") (class "Default")
      (node (ref "R3") (pin "2") (pinfunction "2_2") (pintype "passive"))
      (node (ref "R4") (pin "1") (pinfunction "1_1") (pintype "passive"))
      (node (ref "U2") (pin "B8") (pinfunction "PLLFLTR_B8") (pintype "bidirectional"))
    )
    (net (code "39") (name "Net-(U2-V_FB)") (class "Default")
      (node (ref "R2") (pin "2") (pinfunction "2_2") (pintype "passive"))
      (node (ref "U2") (pin "B6") (pinfunction "V_FB_B6") (pintype "bidirectional"))
    )
    (net (code "40") (name "OK1E1") (class "Default")
      (node (ref "OK1") (pin "15") (pinfunction "E1_15") (pintype "bidirectional"))
      (node (ref "R25") (pin "2") (pinfunction "2_2") (pintype "passive"))
      (node (ref "U3") (pin "3") (pinfunction "INPUT1_3") (pintype "bidirectional"))
    )
    (net (code "41") (name "OK1E2") (class "Default")
      (node (ref "OK1") (pin "13") (pinfunction "E2_13") (pintype "bidirectional"))
      (node (ref "R26") (pin "2") (pinfunction "2_2") (pintype "passive"))
      (node (ref "U3") (pin "5") (pinfunction "INPUT2_5") (pintype "bidirectional"))
    )
    (net (code "42") (name "OK1E3") (class "Default")
      (node (ref "OK1") (pin "11") (pinfunction "E3_11") (pintype "bidirectional"))
      (node (ref "R27") (pin "2") (pinfunction "2_2") (pintype "passive"))
      (node (ref "U3") (pin "7") (pinfunction "INPUT3_7") (pintype "bidirectional"))
    )
    (net (code "43") (name "OK1E4") (class "Default")
      (node (ref "OK1") (pin "9") (pinfunction "E4_9") (pintype "bidirectional"))
      (node (ref "R28") (pin "2") (pinfunction "2_2") (pintype "passive"))
      (node (ref "U3") (pin "9") (pinfunction "INPUT4_9") (pintype "bidirectional"))
    )
    (net (code "44") (name "OK2E1") (class "Default")
      (node (ref "OK2") (pin "15") (pinfunction "E1_15") (pintype "bidirectional"))
      (node (ref "R21") (pin "2") (pinfunction "2_2") (pintype "passive"))
      (node (ref "U4") (pin "3") (pinfunction "INPUT1_3") (pintype "bidirectional"))
    )
    (net (code "45") (name "OK2E2") (class "Default")
      (node (ref "OK2") (pin "13") (pinfunction "E2_13") (pintype "bidirectional"))
      (node (ref "R22") (pin "2") (pinfunction "2_2") (pintype "passive"))
      (node (ref "U4") (pin "5") (pinfunction "INPUT2_5") (pintype "bidirectional"))
    )
    (net (code "46") (name "OK2E3") (class "Default")
      (node (ref "OK2") (pin "11") (pinfunction "E3_11") (pintype "bidirectional"))
      (node (ref "R23") (pin "2") (pinfunction "2_2") (pintype "passive"))
      (node (ref "U4") (pin "7") (pinfunction "INPUT3_7") (pintype "bidirectional"))
    )
    (net (code "47") (name "OK2E4") (class "Default")
      (node (ref "OK2") (pin "9") (pinfunction "E4_9") (pintype "bidirectional"))
      (node (ref "R24") (pin "2") (pinfunction "2_2") (pintype "passive"))
      (node (ref "U4") (pin "9") (pinfunction "INPUT4_9") (pintype "bidirectional"))
    )
    (net (code "48") (name "P3") (class "Default")
      (node (ref "R33") (pin "1") (pinfunction "1_1") (pintype "passive"))
      (node (ref "SJ2") (pin "2") (pinfunction "2_2") (pintype "passive"))
      (node (ref "U1") (pin "17") (pinfunction "VCC3V_17") (pintype "bidirectional"))
      (node (ref "U1") (pin "47") (pinfunction "VCC3V_47") (pintype "bidirectional"))
    )
    (net (code "49") (name "P3_SW") (class "Default")
      (node (ref "J4") (pin "2") (pinfunction "2_2") (pintype "bidirectional"))
      (node (ref "J8") (pin "4") (pinfunction "4_4") (pintype "bidirectional"))
      (node (ref "SJ2") (pin "1") (pinfunction "1_1") (pintype "passive"))
    )
    (net (code "50") (name "P18_SW1") (class "Default")
      (node (ref "OK1") (pin "1") (pinfunction "A1_1") (pintype "bidirectional"))
      (node (ref "R5") (pin "1") (pinfunction "1_1") (pintype "passive"))
    )
    (net (code "51") (name "P18_SW2") (class "Default")
      (node (ref "OK1") (pin "5") (pinfunction "A3_5") (pintype "bidirectional"))
      (node (ref "R6") (pin "1") (pinfunction "1_1") (pintype "passive"))
    )
    (net (code "52") (name "P18_SW3") (class "Default")
      (node (ref "OK2") (pin "1") (pinfunction "A1_1") (pintype "bidirectional"))
      (node (ref "R7") (pin "1") (pinfunction "1_1") (pintype "passive"))
    )
    (net (code "53") (name "P18_SW4") (class "Default")
      (node (ref "OK2") (pin "5") (pinfunction "A3_5") (pintype "bidirectional"))
      (node (ref "R8") (pin "1") (pinfunction "1_1") (pintype "passive"))
    )
    (net (code "54") (name "P18_SW5") (class "Default")
      (node (ref "OK1") (pin "3") (pinfunction "A2_3") (pintype "bidirectional"))
      (node (ref "R9") (pin "1") (pinfunction "1_1") (pintype "passive"))
    )
    (net (code "55") (name "P18_SW6") (class "Default")
      (node (ref "OK1") (pin "7") (pinfunction "A4_7") (pintype "bidirectional"))
      (node (ref "R10") (pin "1") (pinfunction "1_1") (pintype "passive"))
    )
    (net (code "56") (name "P18_SW7") (class "Default")
      (node (ref "OK2") (pin "3") (pinfunction "A2_3") (pintype "bidirectional"))
      (node (ref "R11") (pin "1") (pinfunction "1_1") (pintype "passive"))
    )
    (net (code "57") (name "P18_SW8") (class "Default")
      (node (ref "OK2") (pin "7") (pinfunction "A4_7") (pintype "bidirectional"))
      (node (ref "R12") (pin "1") (pinfunction "1_1") (pintype "passive"))
    )
    (net (code "58") (name "PBATT_SW") (class "Default")
      (node (ref "J4") (pin "3") (pinfunction "3_3") (pintype "bidirectional"))
      (node (ref "J8") (pin "5") (pinfunction "5_5") (pintype "bidirectional"))
      (node (ref "SJ1") (pin "1") (pinfunction "1_1") (pintype "passive"))
    )
    (net (code "59") (name "PGND") (class "Default")
      (node (ref "C3") (pin "2") (pinfunction "2_2") (pintype "passive"))
      (node (ref "C4") (pin "2") (pinfunction "2_2") (pintype "passive"))
      (node (ref "C5") (pin "K1") (pinfunction "K_K1") (pintype "passive"))
      (node (ref "H1") (pin "P$1") (pinfunction "MOUNT_P$1") (pintype "passive"))
      (node (ref "H2") (pin "P$1") (pinfunction "MOUNT_P$1") (pintype "passive"))
      (node (ref "H3") (pin "P$1") (pinfunction "MOUNT_P$1") (pintype "passive"))
      (node (ref "HBL") (pin "P$1") (pinfunction "MOUNT_P$1") (pintype "passive"))
      (node (ref "J5") (pin "1") (pinfunction "1_1") (pintype "bidirectional"))
      (node (ref "J5") (pin "4") (pinfunction "4_4") (pintype "bidirectional"))
      (node (ref "J6") (pin "1") (pinfunction "1_1") (pintype "bidirectional"))
      (node (ref "J6") (pin "4") (pinfunction "4_4") (pintype "bidirectional"))
      (node (ref "R1") (pin "2") (pinfunction "2_2") (pintype "passive"))
      (node (ref "R21") (pin "1") (pinfunction "1_1") (pintype "passive"))
      (node (ref "R22") (pin "1") (pinfunction "1_1") (pintype "passive"))
      (node (ref "R23") (pin "1") (pinfunction "1_1") (pintype "passive"))
      (node (ref "R24") (pin "1") (pinfunction "1_1") (pintype "passive"))
      (node (ref "R25") (pin "1") (pinfunction "1_1") (pintype "passive"))
      (node (ref "R26") (pin "1") (pinfunction "1_1") (pintype "passive"))
      (node (ref "R27") (pin "1") (pinfunction "1_1") (pintype "passive"))
      (node (ref "R28") (pin "1") (pinfunction "1_1") (pintype "passive"))
      (node (ref "SJ4") (pin "2") (pinfunction "2_2") (pintype "passive"))
      (node (ref "U2") (pin "A1") (pinfunction "PGND_A1") (pintype "bidirectional"))
      (node (ref "U2") (pin "A11") (pinfunction "PGND_A11") (pintype "bidirectional"))
      (node (ref "U2") (pin "A12") (pinfunction "PGND_A12") (pintype "bidirectional"))
      (node (ref "U2") (pin "A2") (pinfunction "PGND_A2") (pintype "bidirectional"))
      (node (ref "U2") (pin "A3") (pinfunction "PGND_A3") (pintype "bidirectional"))
      (node (ref "U2") (pin "A5") (pinfunction "SENSE-_A5") (pintype "bidirectional"))
      (node (ref "U2") (pin "A7") (pinfunction "SGND_A7") (pintype "bidirectional"))
      (node (ref "U2") (pin "B1") (pinfunction "PGND_B1") (pintype "bidirectional"))
      (node (ref "U2") (pin "B10") (pinfunction "PGND_B10") (pintype "bidirectional"))
      (node (ref "U2") (pin "B11") (pinfunction "PGND_B11") (pintype "bidirectional"))
      (node (ref "U2") (pin "B12") (pinfunction "PGND_B12") (pintype "bidirectional"))
      (node (ref "U2") (pin "B2") (pinfunction "PGND_B2") (pintype "bidirectional"))
      (node (ref "U2") (pin "B3") (pinfunction "PGND_B3") (pintype "bidirectional"))
      (node (ref "U2") (pin "B4") (pinfunction "PGND_B4") (pintype "bidirectional"))
      (node (ref "U2") (pin "C1") (pinfunction "PGND_C1") (pintype "bidirectional"))
      (node (ref "U2") (pin "C10") (pinfunction "PGND_C10") (pintype "bidirectional"))
      (node (ref "U2") (pin "C11") (pinfunction "PGND_C11") (pintype "bidirectional"))
      (node (ref "U2") (pin "C12") (pinfunction "PGND_C12") (pintype "bidirectional"))
      (node (ref "U2") (pin "C2") (pinfunction "PGND_C2") (pintype "bidirectional"))
      (node (ref "U2") (pin "C3") (pinfunction "PGND_C3") (pintype "bidirectional"))
      (node (ref "U2") (pin "C4") (pinfunction "PGND_C4") (pintype "bidirectional"))
      (node (ref "U2") (pin "C5") (pinfunction "PGND_C5") (pintype "bidirectional"))
      (node (ref "U2") (pin "C6") (pinfunction "PGND_C6") (pintype "bidirectional"))
      (node (ref "U2") (pin "C7") (pinfunction "PGND_C7") (pintype "bidirectional"))
      (node (ref "U2") (pin "C8") (pinfunction "PGND_C8") (pintype "bidirectional"))
      (node (ref "U2") (pin "C9") (pinfunction "PGND_C9") (pintype "bidirectional"))
      (node (ref "U2") (pin "D1") (pinfunction "PGND_D1") (pintype "bidirectional"))
      (node (ref "U2") (pin "D10") (pinfunction "PGND_D10") (pintype "bidirectional"))
      (node (ref "U2") (pin "D11") (pinfunction "PGND_D11") (pintype "bidirectional"))
      (node (ref "U2") (pin "D12") (pinfunction "PGND_D12") (pintype "bidirectional"))
      (node (ref "U2") (pin "D2") (pinfunction "PGND_D2") (pintype "bidirectional"))
      (node (ref "U2") (pin "D3") (pinfunction "PGND_D3") (pintype "bidirectional"))
      (node (ref "U2") (pin "D4") (pinfunction "PGND_D4") (pintype "bidirectional"))
      (node (ref "U2") (pin "D5") (pinfunction "PGND_D5") (pintype "bidirectional"))
      (node (ref "U2") (pin "D6") (pinfunction "PGND_D6") (pintype "bidirectional"))
      (node (ref "U2") (pin "D7") (pinfunction "PGND_D7") (pintype "bidirectional"))
      (node (ref "U2") (pin "D8") (pinfunction "PGND_D8") (pintype "bidirectional"))
      (node (ref "U2") (pin "D9") (pinfunction "PGND_D9") (pintype "bidirectional"))
      (node (ref "U2") (pin "E10") (pinfunction "PGND_E10") (pintype "bidirectional"))
      (node (ref "U2") (pin "E11") (pinfunction "PGND_E11") (pintype "bidirectional"))
      (node (ref "U2") (pin "E12") (pinfunction "PGND_E12") (pintype "bidirectional"))
      (node (ref "U2") (pin "E3") (pinfunction "PGND_E3") (pintype "bidirectional"))
      (node (ref "U2") (pin "E4") (pinfunction "PGND_E4") (pintype "bidirectional"))
      (node (ref "U2") (pin "E5") (pinfunction "PGND_E5") (pintype "bidirectional"))
      (node (ref "U2") (pin "E6") (pinfunction "PGND_E6") (pintype "bidirectional"))
      (node (ref "U2") (pin "E7") (pinfunction "PGND_E7") (pintype "bidirectional"))
      (node (ref "U2") (pin "E8") (pinfunction "PGND_E8") (pintype "bidirectional"))
      (node (ref "U2") (pin "E9") (pinfunction "PGND_E9") (pintype "bidirectional"))
      (node (ref "U3") (pin "1") (pinfunction "GND_1") (pintype "bidirectional"))
      (node (ref "U3") (pin "10") (pinfunction "GND_10") (pintype "bidirectional"))
      (node (ref "U4") (pin "1") (pinfunction "GND_1") (pintype "bidirectional"))
      (node (ref "U4") (pin "10") (pinfunction "GND_10") (pintype "bidirectional"))
    )
    (net (code "60") (name "PGOOD_PMA") (class "Default")
      (node (ref "U2") (pin "B5") (pinfunction "PGOOD_B5") (pintype "bidirectional"))
    )
    (net (code "61") (name "RSENSE") (class "Default")
      (node (ref "R1") (pin "1") (pinfunction "1_1") (pintype "passive"))
      (node (ref "U2") (pin "A4") (pinfunction "SENSE+_A4") (pintype "bidirectional"))
      (node (ref "U2") (pin "F10") (pinfunction "R_SENSE_F10") (pintype "bidirectional"))
      (node (ref "U2") (pin "F11") (pinfunction "R_SENSE_F11") (pintype "bidirectional"))
      (node (ref "U2") (pin "F12") (pinfunction "R_SENSE_F12") (pintype "bidirectional"))
      (node (ref "U2") (pin "G10") (pinfunction "R_SENSE_G10") (pintype "bidirectional"))
      (node (ref "U2") (pin "G11") (pinfunction "R_SENSE_G11") (pintype "bidirectional"))
      (node (ref "U2") (pin "G12") (pinfunction "R_SENSE_G12") (pintype "bidirectional"))
      (node (ref "U2") (pin "G5") (pinfunction "R_SENSE_G5") (pintype "bidirectional"))
      (node (ref "U2") (pin "G6") (pinfunction "R_SENSE_G6") (pintype "bidirectional"))
      (node (ref "U2") (pin "G7") (pinfunction "R_SENSE_G7") (pintype "bidirectional"))
      (node (ref "U2") (pin "G8") (pinfunction "R_SENSE_G8") (pintype "bidirectional"))
      (node (ref "U2") (pin "G9") (pinfunction "R_SENSE_G9") (pintype "bidirectional"))
      (node (ref "U2") (pin "H10") (pinfunction "R_SENSE_H10") (pintype "bidirectional"))
      (node (ref "U2") (pin "H11") (pinfunction "R_SENSE_H11") (pintype "bidirectional"))
      (node (ref "U2") (pin "H12") (pinfunction "R_SENSE_H12") (pintype "bidirectional"))
      (node (ref "U2") (pin "H5") (pinfunction "R_SENSE_H5") (pintype "bidirectional"))
      (node (ref "U2") (pin "H6") (pinfunction "R_SENSE_H6") (pintype "bidirectional"))
      (node (ref "U2") (pin "H7") (pinfunction "R_SENSE_H7") (pintype "bidirectional"))
      (node (ref "U2") (pin "H8") (pinfunction "R_SENSE_H8") (pintype "bidirectional"))
      (node (ref "U2") (pin "H9") (pinfunction "R_SENSE_H9") (pintype "bidirectional"))
      (node (ref "U2") (pin "J5") (pinfunction "R_SENSE_J5") (pintype "bidirectional"))
      (node (ref "U2") (pin "J6") (pinfunction "R_SENSE_J6") (pintype "bidirectional"))
      (node (ref "U2") (pin "J7") (pinfunction "R_SENSE_J7") (pintype "bidirectional"))
      (node (ref "U2") (pin "K5") (pinfunction "R_SENSE_K5") (pintype "bidirectional"))
      (node (ref "U2") (pin "K6") (pinfunction "R_SENSE_K6") (pintype "bidirectional"))
      (node (ref "U2") (pin "L5") (pinfunction "R_SENSE_L5") (pintype "bidirectional"))
      (node (ref "U2") (pin "L6") (pinfunction "R_SENSE_L6") (pintype "bidirectional"))
      (node (ref "U2") (pin "M5") (pinfunction "R_SENSE_M5") (pintype "bidirectional"))
      (node (ref "U2") (pin "M6") (pinfunction "R_SENSE_M6") (pintype "bidirectional"))
    )
    (net (code "62") (name "RUN_PMA") (class "Default")
      (node (ref "U2") (pin "A8") (pinfunction "RUN_A8") (pintype "bidirectional"))
    )
    (net (code "63") (name "SGND") (class "Default")
      (node (ref "J4") (pin "6") (pinfunction "6_6") (pintype "bidirectional"))
      (node (ref "J5") (pin "12") (pinfunction "12_12") (pintype "bidirectional"))
      (node (ref "J5") (pin "9") (pinfunction "9_9") (pintype "bidirectional"))
      (node (ref "J6") (pin "12") (pinfunction "12_12") (pintype "bidirectional"))
      (node (ref "J6") (pin "9") (pinfunction "9_9") (pintype "bidirectional"))
      (node (ref "OK1") (pin "2") (pinfunction "K1_2") (pintype "bidirectional"))
      (node (ref "OK1") (pin "4") (pinfunction "K2_4") (pintype "bidirectional"))
      (node (ref "OK1") (pin "6") (pinfunction "K3_6") (pintype "bidirectional"))
      (node (ref "OK1") (pin "8") (pinfunction "K4_8") (pintype "bidirectional"))
      (node (ref "OK2") (pin "2") (pinfunction "K1_2") (pintype "bidirectional"))
      (node (ref "OK2") (pin "4") (pinfunction "K2_4") (pintype "bidirectional"))
      (node (ref "OK2") (pin "6") (pinfunction "K3_6") (pintype "bidirectional"))
      (node (ref "OK2") (pin "8") (pinfunction "K4_8") (pintype "bidirectional"))
      (node (ref "OK3") (pin "15") (pinfunction "E1_15") (pintype "bidirectional"))
      (node (ref "R4") (pin "2") (pinfunction "2_2") (pintype "passive"))
      (node (ref "SJ3") (pin "2") (pinfunction "2_2") (pintype "passive"))
    )
    (net (code "64") (name "SW_P18H1") (class "Default")
      (node (ref "R9") (pin "2") (pinfunction "2_2") (pintype "passive"))
      (node (ref "U1") (pin "35") (pinfunction "SDHC_DAT0_35") (pintype "bidirectional"))
    )
    (net (code "65") (name "SW_P18H2") (class "Default")
      (node (ref "R10") (pin "2") (pinfunction "2_2") (pintype "passive"))
      (node (ref "U1") (pin "34") (pinfunction "UART1_TX_34") (pintype "bidirectional"))
    )
    (net (code "66") (name "SW_P18H3") (class "Default")
      (node (ref "R11") (pin "2") (pinfunction "2_2") (pintype "passive"))
      (node (ref "U1") (pin "33") (pinfunction "SDHC_CMD_33") (pintype "bidirectional"))
    )
    (net (code "67") (name "SW_P18H4") (class "Default")
      (node (ref "R12") (pin "2") (pinfunction "2_2") (pintype "passive"))
      (node (ref "U1") (pin "32") (pinfunction "UART1_RX_32") (pintype "bidirectional"))
    )
    (net (code "68") (name "SW_P18L1") (class "Default")
      (node (ref "R5") (pin "2") (pinfunction "2_2") (pintype "passive"))
      (node (ref "U1") (pin "39") (pinfunction "SDHC_DAT2_39") (pintype "bidirectional"))
    )
    (net (code "69") (name "SW_P18L2") (class "Default")
      (node (ref "R6") (pin "2") (pinfunction "2_2") (pintype "passive"))
      (node (ref "U1") (pin "38") (pinfunction "UART1_CTS_38") (pintype "bidirectional"))
    )
    (net (code "70") (name "SW_P18L3") (class "Default")
      (node (ref "R7") (pin "2") (pinfunction "2_2") (pintype "passive"))
      (node (ref "U1") (pin "37") (pinfunction "SDHC_DAT1_37") (pintype "bidirectional"))
    )
    (net (code "71") (name "SW_P18L4") (class "Default")
      (node (ref "R8") (pin "2") (pinfunction "2_2") (pintype "passive"))
      (node (ref "U1") (pin "36") (pinfunction "UART1_RTS_36") (pintype "bidirectional"))
    )
    (net (code "72") (name "SW_RUNPMA") (class "Default")
      (node (ref "U1") (pin "23") (pinfunction "T2IN_23") (pintype "bidirectional"))
    )
    (net (code "73") (name "SW_TP1") (class "Default")
      (node (ref "J4") (pin "7") (pinfunction "7_7") (pintype "bidirectional"))
      (node (ref "OK3") (pin "2") (pinfunction "K1_2") (pintype "bidirectional"))
      (node (ref "U1") (pin "31") (pinfunction "SDHC_CLK_31") (pintype "bidirectional"))
    )
    (net (code "74") (name "TP1_OUT") (class "Default")
      (node (ref "J4") (pin "8") (pinfunction "8_8") (pintype "bidirectional"))
      (node (ref "J5") (pin "3") (pinfunction "3_3") (pintype "bidirectional"))
      (node (ref "J5") (pin "6") (pinfunction "6_6") (pintype "bidirectional"))
      (node (ref "J6") (pin "3") (pinfunction "3_3") (pintype "bidirectional"))
      (node (ref "J6") (pin "6") (pinfunction "6_6") (pintype "bidirectional"))
      (node (ref "OK3") (pin "16") (pinfunction "C1_16") (pintype "bidirectional"))
      (node (ref "R34") (pin "1") (pinfunction "1_1") (pintype "passive"))
    )
    (net (code "75") (name "VBATT_IN") (class "Default")
      (node (ref "C1") (pin "A1") (pinfunction "A_A1") (pintype "passive"))
      (node (ref "L2") (pin "1") (pinfunction "1_1") (pintype "bidirectional"))
      (node (ref "SJ1") (pin "2") (pinfunction "2_2") (pintype "passive"))
    )
    (net (code "76") (name "VIN") (class "Default")
      (node (ref "C2") (pin "1") (pinfunction "1_1") (pintype "passive"))
      (node (ref "L2") (pin "2") (pinfunction "2_2") (pintype "bidirectional"))
      (node (ref "U2") (pin "J10") (pinfunction "V_IN_J10") (pintype "bidirectional"))
      (node (ref "U2") (pin "J11") (pinfunction "V_IN_J11") (pintype "bidirectional"))
      (node (ref "U2") (pin "J12") (pinfunction "V_IN_J12") (pintype "bidirectional"))
      (node (ref "U2") (pin "K10") (pinfunction "V_IN_K10") (pintype "bidirectional"))
      (node (ref "U2") (pin "K11") (pinfunction "V_IN_K11") (pintype "bidirectional"))
      (node (ref "U2") (pin "K12") (pinfunction "V_IN_K12") (pintype "bidirectional"))
      (node (ref "U2") (pin "L10") (pinfunction "V_IN_L10") (pintype "bidirectional"))
      (node (ref "U2") (pin "L11") (pinfunction "V_IN_L11") (pintype "bidirectional"))
      (node (ref "U2") (pin "L12") (pinfunction "V_IN_L12") (pintype "bidirectional"))
      (node (ref "U2") (pin "M10") (pinfunction "V_IN_M10") (pintype "bidirectional"))
      (node (ref "U2") (pin "M11") (pinfunction "V_IN_M11") (pintype "bidirectional"))
      (node (ref "U2") (pin "M12") (pinfunction "V_IN_M12") (pintype "bidirectional"))
    )
    (net (code "77") (name "VOUT") (class "Default")
      (node (ref "C3") (pin "1") (pinfunction "1_1") (pintype "passive"))
      (node (ref "C4") (pin "1") (pinfunction "1_1") (pintype "passive"))
      (node (ref "L3") (pin "1") (pinfunction "1_1") (pintype "bidirectional"))
      (node (ref "U2") (pin "E1") (pinfunction "V_OUT_E1") (pintype "bidirectional"))
      (node (ref "U2") (pin "E2") (pinfunction "V_OUT_E2") (pintype "bidirectional"))
      (node (ref "U2") (pin "F1") (pinfunction "V_OUT_F1") (pintype "bidirectional"))
      (node (ref "U2") (pin "F2") (pinfunction "V_OUT_F2") (pintype "bidirectional"))
      (node (ref "U2") (pin "F3") (pinfunction "V_OUT_F3") (pintype "bidirectional"))
      (node (ref "U2") (pin "F4") (pinfunction "V_OUT_F4") (pintype "bidirectional"))
      (node (ref "U2") (pin "G1") (pinfunction "V_OUT_G1") (pintype "bidirectional"))
      (node (ref "U2") (pin "G2") (pinfunction "V_OUT_G2") (pintype "bidirectional"))
      (node (ref "U2") (pin "G3") (pinfunction "V_OUT_G3") (pintype "bidirectional"))
      (node (ref "U2") (pin "G4") (pinfunction "V_OUT_G4") (pintype "bidirectional"))
      (node (ref "U2") (pin "H2") (pinfunction "V_OUT_H2") (pintype "bidirectional"))
      (node (ref "U2") (pin "H3") (pinfunction "V_OUT_H3") (pintype "bidirectional"))
      (node (ref "U2") (pin "H4") (pinfunction "V_OUT_H4") (pintype "bidirectional"))
      (node (ref "U2") (pin "VOUT") (pinfunction "V_OUT_VOUT") (pintype "bidirectional"))
    )
    (net (code "78") (name "VOUTA") (class "Default")
      (node (ref "C5") (pin "A1") (pinfunction "A_A1") (pintype "passive"))
      (node (ref "L3") (pin "2") (pinfunction "2_2") (pintype "bidirectional"))
      (node (ref "Q11") (pin "D") (pinfunction "D_D") (pintype "bidirectional"))
      (node (ref "Q13") (pin "D") (pinfunction "D_D") (pintype "bidirectional"))
      (node (ref "Q15") (pin "D") (pinfunction "D_D") (pintype "bidirectional"))
      (node (ref "Q9") (pin "D") (pinfunction "D_D") (pintype "bidirectional"))
      (node (ref "R13") (pin "1") (pinfunction "1_1") (pintype "passive"))
      (node (ref "R14") (pin "1") (pinfunction "1_1") (pintype "passive"))
      (node (ref "R15") (pin "1") (pinfunction "1_1") (pintype "passive"))
      (node (ref "R16") (pin "1") (pinfunction "1_1") (pintype "passive"))
      (node (ref "R17") (pin "1") (pinfunction "1_1") (pintype "passive"))
      (node (ref "R18") (pin "1") (pinfunction "1_1") (pintype "passive"))
      (node (ref "R19") (pin "1") (pinfunction "1_1") (pintype "passive"))
      (node (ref "R20") (pin "1") (pinfunction "1_1") (pintype "passive"))
      (node (ref "R29") (pin "2") (pinfunction "2_2") (pintype "passive"))
      (node (ref "R30") (pin "2") (pinfunction "2_2") (pintype "passive"))
      (node (ref "R31") (pin "2") (pinfunction "2_2") (pintype "passive"))
      (node (ref "R32") (pin "2") (pinfunction "2_2") (pintype "passive"))
      (node (ref "U3") (pin "11") (pinfunction "V+_11") (pintype "bidirectional"))
      (node (ref "U3") (pin "13") (pinfunction "SENSE4_13") (pintype "bidirectional"))
      (node (ref "U3") (pin "15") (pinfunction "SENSE3_15") (pintype "bidirectional"))
      (node (ref "U3") (pin "17") (pinfunction "SENSE2_17") (pintype "bidirectional"))
      (node (ref "U3") (pin "19") (pinfunction "SENSE1_19") (pintype "bidirectional"))
      (node (ref "U3") (pin "20") (pinfunction "V+_20") (pintype "bidirectional"))
      (node (ref "U4") (pin "11") (pinfunction "V+_11") (pintype "bidirectional"))
      (node (ref "U4") (pin "13") (pinfunction "SENSE4_13") (pintype "bidirectional"))
      (node (ref "U4") (pin "15") (pinfunction "SENSE3_15") (pintype "bidirectional"))
      (node (ref "U4") (pin "17") (pinfunction "SENSE2_17") (pintype "bidirectional"))
      (node (ref "U4") (pin "19") (pinfunction "SENSE1_19") (pintype "bidirectional"))
      (node (ref "U4") (pin "20") (pinfunction "V+_20") (pintype "bidirectional"))
    )
    (net (code "79") (name "unconnected-(J2-+5V_SW-Pad33)") (class "Default")
      (node (ref "J2") (pin "33") (pinfunction "+5V_SW_33") (pintype "bidirectional"))
    )
    (net (code "80") (name "unconnected-(J2-+5V_SYS-Pad77)") (class "Default")
      (node (ref "J2") (pin "77") (pinfunction "+5V_SYS_77") (pintype "bidirectional"))
    )
    (net (code "81") (name "unconnected-(J2-+5V_SYS-Pad78)") (class "Default")
      (node (ref "J2") (pin "78") (pinfunction "+5V_SYS_78") (pintype "bidirectional"))
    )
    (net (code "82") (name "unconnected-(J2-+5V_USB-Pad32)") (class "Default")
      (node (ref "J2") (pin "32") (pinfunction "+5V_USB_32") (pintype "bidirectional"))
    )
    (net (code "83") (name "unconnected-(J2--CTS_MHX-Pad35)") (class "Default")
      (node (ref "J2") (pin "35") (pinfunction "-CTS_MHX_35") (pintype "bidirectional"))
    )
    (net (code "84") (name "unconnected-(J2--DSR_MHX-Pad37)") (class "Default")
      (node (ref "J2") (pin "37") (pinfunction "-DSR_MHX_37") (pintype "bidirectional"))
    )
    (net (code "85") (name "unconnected-(J2--DTR_MHX-Pad38)") (class "Default")
      (node (ref "J2") (pin "38") (pinfunction "-DTR_MHX_38") (pintype "bidirectional"))
    )
    (net (code "86") (name "unconnected-(J2--FAULT-Pad25)") (class "Default")
      (node (ref "J2") (pin "25") (pinfunction "-FAULT_25") (pintype "bidirectional"))
    )
    (net (code "87") (name "unconnected-(J2--RESET-Pad29)") (class "Default")
      (node (ref "J2") (pin "29") (pinfunction "-RESET_29") (pintype "bidirectional"))
    )
    (net (code "88") (name "unconnected-(J2--RST_MHX-Pad34)") (class "Default")
      (node (ref "J2") (pin "34") (pinfunction "-RST_MHX_34") (pintype "bidirectional"))
    )
    (net (code "89") (name "unconnected-(J2--RTS_MHX-Pad36)") (class "Default")
      (node (ref "J2") (pin "36") (pinfunction "-RTS_MHX_36") (pintype "bidirectional"))
    )
    (net (code "90") (name "unconnected-(J2-OFF_VCC-Pad31)") (class "Default")
      (node (ref "J2") (pin "31") (pinfunction "OFF_VCC_31") (pintype "bidirectional"))
    )
    (net (code "91") (name "unconnected-(J2-P1.0-Pad68)") (class "Default")
      (node (ref "J2") (pin "68") (pinfunction "P1.0_68") (pintype "bidirectional"))
    )
    (net (code "92") (name "unconnected-(J2-P1.1-Pad67)") (class "Default")
      (node (ref "J2") (pin "67") (pinfunction "P1.1_67") (pintype "bidirectional"))
    )
    (net (code "93") (name "unconnected-(J2-P1.2-Pad66)") (class "Default")
      (node (ref "J2") (pin "66") (pinfunction "P1.2_66") (pintype "bidirectional"))
    )
    (net (code "94") (name "unconnected-(J2-P1.3-Pad65)") (class "Default")
      (node (ref "J2") (pin "65") (pinfunction "P1.3_65") (pintype "bidirectional"))
    )
    (net (code "95") (name "unconnected-(J2-P1.4-Pad64)") (class "Default")
      (node (ref "J2") (pin "64") (pinfunction "P1.4_64") (pintype "bidirectional"))
    )
    (net (code "96") (name "unconnected-(J2-P1.5-Pad63)") (class "Default")
      (node (ref "J2") (pin "63") (pinfunction "P1.5_63") (pintype "bidirectional"))
    )
    (net (code "97") (name "unconnected-(J2-P1.6-Pad62)") (class "Default")
      (node (ref "J2") (pin "62") (pinfunction "P1.6_62") (pintype "bidirectional"))
    )
    (net (code "98") (name "unconnected-(J2-P1.7-Pad61)") (class "Default")
      (node (ref "J2") (pin "61") (pinfunction "P1.7_61") (pintype "bidirectional"))
    )
    (net (code "99") (name "unconnected-(J2-P2.0-Pad76)") (class "Default")
      (node (ref "J2") (pin "76") (pinfunction "P2.0_76") (pintype "bidirectional"))
    )
    (net (code "100") (name "unconnected-(J2-P2.1-Pad75)") (class "Default")
      (node (ref "J2") (pin "75") (pinfunction "P2.1_75") (pintype "bidirectional"))
    )
    (net (code "101") (name "unconnected-(J2-P2.2-Pad74)") (class "Default")
      (node (ref "J2") (pin "74") (pinfunction "P2.2_74") (pintype "bidirectional"))
    )
    (net (code "102") (name "unconnected-(J2-P2.3-Pad73)") (class "Default")
      (node (ref "J2") (pin "73") (pinfunction "P2.3_73") (pintype "bidirectional"))
    )
    (net (code "103") (name "unconnected-(J2-P2.4-Pad72)") (class "Default")
      (node (ref "J2") (pin "72") (pinfunction "P2.4_72") (pintype "bidirectional"))
    )
    (net (code "104") (name "unconnected-(J2-P2.5-Pad71)") (class "Default")
      (node (ref "J2") (pin "71") (pinfunction "P2.5_71") (pintype "bidirectional"))
    )
    (net (code "105") (name "unconnected-(J2-P2.6-Pad70)") (class "Default")
      (node (ref "J2") (pin "70") (pinfunction "P2.6_70") (pintype "bidirectional"))
    )
    (net (code "106") (name "unconnected-(J2-P2.7-Pad69)") (class "Default")
      (node (ref "J2") (pin "69") (pinfunction "P2.7_69") (pintype "bidirectional"))
    )
    (net (code "107") (name "unconnected-(J2-P3.0-Pad24)") (class "Default")
      (node (ref "J2") (pin "24") (pinfunction "P3.0_24") (pintype "bidirectional"))
    )
    (net (code "108") (name "unconnected-(J2-P3.1-Pad23)") (class "Default")
      (node (ref "J2") (pin "23") (pinfunction "P3.1_23") (pintype "bidirectional"))
    )
    (net (code "109") (name "unconnected-(J2-P3.2-Pad22)") (class "Default")
      (node (ref "J2") (pin "22") (pinfunction "P3.2_22") (pintype "bidirectional"))
    )
    (net (code "110") (name "unconnected-(J2-P3.3-Pad21)") (class "Default")
      (node (ref "J2") (pin "21") (pinfunction "P3.3_21") (pintype "bidirectional"))
    )
    (net (code "111") (name "unconnected-(J2-P3.4-Pad20)") (class "Default")
      (node (ref "J2") (pin "20") (pinfunction "P3.4_20") (pintype "bidirectional"))
    )
    (net (code "112") (name "unconnected-(J2-P3.5-Pad19)") (class "Default")
      (node (ref "J2") (pin "19") (pinfunction "P3.5_19") (pintype "bidirectional"))
    )
    (net (code "113") (name "unconnected-(J2-P3.6-Pad18)") (class "Default")
      (node (ref "J2") (pin "18") (pinfunction "P3.6_18") (pintype "bidirectional"))
    )
    (net (code "114") (name "unconnected-(J2-P3.7-Pad17)") (class "Default")
      (node (ref "J2") (pin "17") (pinfunction "P3.7_17") (pintype "bidirectional"))
    )
    (net (code "115") (name "unconnected-(J2-P4.0-Pad16)") (class "Default")
      (node (ref "J2") (pin "16") (pinfunction "P4.0_16") (pintype "bidirectional"))
    )
    (net (code "116") (name "unconnected-(J2-P4.1-Pad15)") (class "Default")
      (node (ref "J2") (pin "15") (pinfunction "P4.1_15") (pintype "bidirectional"))
    )
    (net (code "117") (name "unconnected-(J2-P4.2-Pad14)") (class "Default")
      (node (ref "J2") (pin "14") (pinfunction "P4.2_14") (pintype "bidirectional"))
    )
    (net (code "118") (name "unconnected-(J2-P4.3-Pad13)") (class "Default")
      (node (ref "J2") (pin "13") (pinfunction "P4.3_13") (pintype "bidirectional"))
    )
    (net (code "119") (name "unconnected-(J2-P4.4-Pad12)") (class "Default")
      (node (ref "J2") (pin "12") (pinfunction "P4.4_12") (pintype "bidirectional"))
    )
    (net (code "120") (name "unconnected-(J2-P4.5-Pad11)") (class "Default")
      (node (ref "J2") (pin "11") (pinfunction "P4.5_11") (pintype "bidirectional"))
    )
    (net (code "121") (name "unconnected-(J2-P4.6-Pad10)") (class "Default")
      (node (ref "J2") (pin "10") (pinfunction "P4.6_10") (pintype "bidirectional"))
    )
    (net (code "122") (name "unconnected-(J2-P4.7-Pad9)") (class "Default")
      (node (ref "J2") (pin "9") (pinfunction "P4.7_9") (pintype "bidirectional"))
    )
    (net (code "123") (name "unconnected-(J2-P5.0-Pad8)") (class "Default")
      (node (ref "J2") (pin "8") (pinfunction "P5.0_8") (pintype "bidirectional"))
    )
    (net (code "124") (name "unconnected-(J2-P5.1-Pad7)") (class "Default")
      (node (ref "J2") (pin "7") (pinfunction "P5.1_7") (pintype "bidirectional"))
    )
    (net (code "125") (name "unconnected-(J2-P5.2-Pad6)") (class "Default")
      (node (ref "J2") (pin "6") (pinfunction "P5.2_6") (pintype "bidirectional"))
    )
    (net (code "126") (name "unconnected-(J2-P5.3-Pad5)") (class "Default")
      (node (ref "J2") (pin "5") (pinfunction "P5.3_5") (pintype "bidirectional"))
    )
    (net (code "127") (name "unconnected-(J2-P5.4-Pad4)") (class "Default")
      (node (ref "J2") (pin "4") (pinfunction "P5.4_4") (pintype "bidirectional"))
    )
    (net (code "128") (name "unconnected-(J2-P5.5-Pad3)") (class "Default")
      (node (ref "J2") (pin "3") (pinfunction "P5.5_3") (pintype "bidirectional"))
    )
    (net (code "129") (name "unconnected-(J2-P5.6-Pad2)") (class "Default")
      (node (ref "J2") (pin "2") (pinfunction "P5.6_2") (pintype "bidirectional"))
    )
    (net (code "130") (name "unconnected-(J2-P5.7-Pad1)") (class "Default")
      (node (ref "J2") (pin "1") (pinfunction "P5.7_1") (pintype "bidirectional"))
    )
    (net (code "131") (name "unconnected-(J2-P6.0-Pad60)") (class "Default")
      (node (ref "J2") (pin "60") (pinfunction "P6.0_60") (pintype "bidirectional"))
    )
    (net (code "132") (name "unconnected-(J2-P6.1-Pad59)") (class "Default")
      (node (ref "J2") (pin "59") (pinfunction "P6.1_59") (pintype "bidirectional"))
    )
    (net (code "133") (name "unconnected-(J2-P6.2-Pad58)") (class "Default")
      (node (ref "J2") (pin "58") (pinfunction "P6.2_58") (pintype "bidirectional"))
    )
    (net (code "134") (name "unconnected-(J2-P6.3-Pad57)") (class "Default")
      (node (ref "J2") (pin "57") (pinfunction "P6.3_57") (pintype "bidirectional"))
    )
    (net (code "135") (name "unconnected-(J2-P6.4-Pad56)") (class "Default")
      (node (ref "J2") (pin "56") (pinfunction "P6.4_56") (pintype "bidirectional"))
    )
    (net (code "136") (name "unconnected-(J2-P6.5-Pad55)") (class "Default")
      (node (ref "J2") (pin "55") (pinfunction "P6.5_55") (pintype "bidirectional"))
    )
    (net (code "137") (name "unconnected-(J2-P6.6-Pad54)") (class "Default")
      (node (ref "J2") (pin "54") (pinfunction "P6.6_54") (pintype "bidirectional"))
    )
    (net (code "138") (name "unconnected-(J2-P6.7-Pad53)") (class "Default")
      (node (ref "J2") (pin "53") (pinfunction "P6.7_53") (pintype "bidirectional"))
    )
    (net (code "139") (name "unconnected-(J2-RSVD0-Pad44)") (class "Default")
      (node (ref "J2") (pin "44") (pinfunction "RSVD0_44") (pintype "bidirectional"))
    )
    (net (code "140") (name "unconnected-(J2-RSVD1-Pad45)") (class "Default")
      (node (ref "J2") (pin "45") (pinfunction "RSVD1_45") (pintype "bidirectional"))
    )
    (net (code "141") (name "unconnected-(J2-RSVD2-Pad46)") (class "Default")
      (node (ref "J2") (pin "46") (pinfunction "RSVD2_46") (pintype "bidirectional"))
    )
    (net (code "142") (name "unconnected-(J2-RXD_MHX-Pad40)") (class "Default")
      (node (ref "J2") (pin "40") (pinfunction "RXD_MHX_40") (pintype "bidirectional"))
    )
    (net (code "143") (name "unconnected-(J2-SENSE-Pad27)") (class "Default")
      (node (ref "J2") (pin "27") (pinfunction "SENSE_27") (pintype "bidirectional"))
    )
    (net (code "144") (name "unconnected-(J2-SW0-Pad85)") (class "Default")
      (node (ref "J2") (pin "85") (pinfunction "SW0_85") (pintype "bidirectional"))
    )
    (net (code "145") (name "unconnected-(J2-SW0-Pad86)") (class "Default")
      (node (ref "J2") (pin "86") (pinfunction "SW0_86") (pintype "bidirectional"))
    )
    (net (code "146") (name "unconnected-(J2-SW1-Pad87)") (class "Default")
      (node (ref "J2") (pin "87") (pinfunction "SW1_87") (pintype "bidirectional"))
    )
    (net (code "147") (name "unconnected-(J2-SW1-Pad88)") (class "Default")
      (node (ref "J2") (pin "88") (pinfunction "SW1_88") (pintype "bidirectional"))
    )
    (net (code "148") (name "unconnected-(J2-SW2-Pad89)") (class "Default")
      (node (ref "J2") (pin "89") (pinfunction "SW2_89") (pintype "bidirectional"))
    )
    (net (code "149") (name "unconnected-(J2-SW2-Pad90)") (class "Default")
      (node (ref "J2") (pin "90") (pinfunction "SW2_90") (pintype "bidirectional"))
    )
    (net (code "150") (name "unconnected-(J2-SW3-Pad91)") (class "Default")
      (node (ref "J2") (pin "91") (pinfunction "SW3_91") (pintype "bidirectional"))
    )
    (net (code "151") (name "unconnected-(J2-SW3-Pad92)") (class "Default")
      (node (ref "J2") (pin "92") (pinfunction "SW3_92") (pintype "bidirectional"))
    )
    (net (code "152") (name "unconnected-(J2-SW4-Pad93)") (class "Default")
      (node (ref "J2") (pin "93") (pinfunction "SW4_93") (pintype "bidirectional"))
    )
    (net (code "153") (name "unconnected-(J2-SW4-Pad94)") (class "Default")
      (node (ref "J2") (pin "94") (pinfunction "SW4_94") (pintype "bidirectional"))
    )
    (net (code "154") (name "unconnected-(J2-SW5-Pad95)") (class "Default")
      (node (ref "J2") (pin "95") (pinfunction "SW5_95") (pintype "bidirectional"))
    )
    (net (code "155") (name "unconnected-(J2-SW5-Pad96)") (class "Default")
      (node (ref "J2") (pin "96") (pinfunction "SW5_96") (pintype "bidirectional"))
    )
    (net (code "156") (name "unconnected-(J2-TXD_MHX-Pad39)") (class "Default")
      (node (ref "J2") (pin "39") (pinfunction "TXD_MHX_39") (pintype "bidirectional"))
    )
    (net (code "157") (name "unconnected-(J2-USER0-Pad47)") (class "Default")
      (node (ref "J2") (pin "47") (pinfunction "USER0_47") (pintype "bidirectional"))
    )
    (net (code "158") (name "unconnected-(J2-USER1-Pad48)") (class "Default")
      (node (ref "J2") (pin "48") (pinfunction "USER1_48") (pintype "bidirectional"))
    )
    (net (code "159") (name "unconnected-(J2-USER2-Pad49)") (class "Default")
      (node (ref "J2") (pin "49") (pinfunction "USER2_49") (pintype "bidirectional"))
    )
    (net (code "160") (name "unconnected-(J2-USER3-Pad50)") (class "Default")
      (node (ref "J2") (pin "50") (pinfunction "USER3_50") (pintype "bidirectional"))
    )
    (net (code "161") (name "unconnected-(J2-USER4-Pad51)") (class "Default")
      (node (ref "J2") (pin "51") (pinfunction "USER4_51") (pintype "bidirectional"))
    )
    (net (code "162") (name "unconnected-(J2-USER5-Pad52)") (class "Default")
      (node (ref "J2") (pin "52") (pinfunction "USER5_52") (pintype "bidirectional"))
    )
    (net (code "163") (name "unconnected-(J2-USER6-Pad99)") (class "Default")
      (node (ref "J2") (pin "99") (pinfunction "USER6_99") (pintype "bidirectional"))
    )
    (net (code "164") (name "unconnected-(J2-USER7-Pad100)") (class "Default")
      (node (ref "J2") (pin "100") (pinfunction "USER7_100") (pintype "bidirectional"))
    )
    (net (code "165") (name "unconnected-(J2-USER8-Pad101)") (class "Default")
      (node (ref "J2") (pin "101") (pinfunction "USER8_101") (pintype "bidirectional"))
    )
    (net (code "166") (name "unconnected-(J2-USER9-Pad102)") (class "Default")
      (node (ref "J2") (pin "102") (pinfunction "USER9_102") (pintype "bidirectional"))
    )
    (net (code "167") (name "unconnected-(J2-USER10-Pad103)") (class "Default")
      (node (ref "J2") (pin "103") (pinfunction "USER10_103") (pintype "bidirectional"))
    )
    (net (code "168") (name "unconnected-(J2-USER11-Pad104)") (class "Default")
      (node (ref "J2") (pin "104") (pinfunction "USER11_104") (pintype "bidirectional"))
    )
    (net (code "169") (name "unconnected-(J2-VBACKUP-Pad42)") (class "Default")
      (node (ref "J2") (pin "42") (pinfunction "VBACKUP_42") (pintype "bidirectional"))
    )
    (net (code "170") (name "unconnected-(J2-VBATT-Pad97)") (class "Default")
      (node (ref "J2") (pin "97") (pinfunction "VBATT_97") (pintype "bidirectional"))
    )
    (net (code "171") (name "unconnected-(J2-VBATT-Pad98)") (class "Default")
      (node (ref "J2") (pin "98") (pinfunction "VBATT_98") (pintype "bidirectional"))
    )
    (net (code "172") (name "unconnected-(J2-VCC_SYS-Pad79)") (class "Default")
      (node (ref "J2") (pin "79") (pinfunction "VCC_SYS_79") (pintype "bidirectional"))
    )
    (net (code "173") (name "unconnected-(J2-VCC_SYS-Pad80)") (class "Default")
      (node (ref "J2") (pin "80") (pinfunction "VCC_SYS_80") (pintype "bidirectional"))
    )
    (net (code "174") (name "unconnected-(J2-VEREF+-Pad28)") (class "Default")
      (node (ref "J2") (pin "28") (pinfunction "VEREF+_28") (pintype "bidirectional"))
    )
    (net (code "175") (name "unconnected-(J2-VREF+-Pad26)") (class "Default")
      (node (ref "J2") (pin "26") (pinfunction "VREF+_26") (pintype "bidirectional"))
    )
    (net (code "176") (name "unconnected-(J2-VREF--Pad30)") (class "Default")
      (node (ref "J2") (pin "30") (pinfunction "VREF-_30") (pintype "bidirectional"))
    )
    (net (code "177") (name "unconnected-(J4-Pad9)") (class "Default")
      (node (ref "J4") (pin "9") (pinfunction "9_9") (pintype "bidirectional"))
    )
    (net (code "178") (name "unconnected-(J4-Pad10)") (class "Default")
      (node (ref "J4") (pin "10") (pinfunction "10_10") (pintype "bidirectional"))
    )
    (net (code "179") (name "unconnected-(J5-Pad2)") (class "Default")
      (node (ref "J5") (pin "2") (pinfunction "2_2") (pintype "bidirectional"))
    )
    (net (code "180") (name "unconnected-(J5-Pad5)") (class "Default")
      (node (ref "J5") (pin "5") (pinfunction "5_5") (pintype "bidirectional"))
    )
    (net (code "181") (name "unconnected-(J6-Pad2)") (class "Default")
      (node (ref "J6") (pin "2") (pinfunction "2_2") (pintype "bidirectional"))
    )
    (net (code "182") (name "unconnected-(J6-Pad5)") (class "Default")
      (node (ref "J6") (pin "5") (pinfunction "5_5") (pintype "bidirectional"))
    )
    (net (code "183") (name "unconnected-(J8-Pad3)") (class "Default")
      (node (ref "J8") (pin "3") (pinfunction "3_3") (pintype "bidirectional"))
    )
    (net (code "184") (name "unconnected-(J8-Pad6)") (class "Default")
      (node (ref "J8") (pin "6") (pinfunction "6_6") (pintype "bidirectional"))
    )
    (net (code "185") (name "unconnected-(OK3-A2-Pad3)") (class "Default")
      (node (ref "OK3") (pin "3") (pinfunction "A2_3") (pintype "bidirectional"))
    )
    (net (code "186") (name "unconnected-(OK3-A3-Pad5)") (class "Default")
      (node (ref "OK3") (pin "5") (pinfunction "A3_5") (pintype "bidirectional"))
    )
    (net (code "187") (name "unconnected-(OK3-A4-Pad7)") (class "Default")
      (node (ref "OK3") (pin "7") (pinfunction "A4_7") (pintype "bidirectional"))
    )
    (net (code "188") (name "unconnected-(OK3-C2-Pad14)") (class "Default")
      (node (ref "OK3") (pin "14") (pinfunction "C2_14") (pintype "bidirectional"))
    )
    (net (code "189") (name "unconnected-(OK3-C3-Pad12)") (class "Default")
      (node (ref "OK3") (pin "12") (pinfunction "C3_12") (pintype "bidirectional"))
    )
    (net (code "190") (name "unconnected-(OK3-C4-Pad10)") (class "Default")
      (node (ref "OK3") (pin "10") (pinfunction "C4_10") (pintype "bidirectional"))
    )
    (net (code "191") (name "unconnected-(OK3-E2-Pad13)") (class "Default")
      (node (ref "OK3") (pin "13") (pinfunction "E2_13") (pintype "bidirectional"))
    )
    (net (code "192") (name "unconnected-(OK3-E3-Pad11)") (class "Default")
      (node (ref "OK3") (pin "11") (pinfunction "E3_11") (pintype "bidirectional"))
    )
    (net (code "193") (name "unconnected-(OK3-E4-Pad9)") (class "Default")
      (node (ref "OK3") (pin "9") (pinfunction "E4_9") (pintype "bidirectional"))
    )
    (net (code "194") (name "unconnected-(OK3-K2-Pad4)") (class "Default")
      (node (ref "OK3") (pin "4") (pinfunction "K2_4") (pintype "bidirectional"))
    )
    (net (code "195") (name "unconnected-(OK3-K3-Pad6)") (class "Default")
      (node (ref "OK3") (pin "6") (pinfunction "K3_6") (pintype "bidirectional"))
    )
    (net (code "196") (name "unconnected-(OK3-K4-Pad8)") (class "Default")
      (node (ref "OK3") (pin "8") (pinfunction "K4_8") (pintype "bidirectional"))
    )
    (net (code "197") (name "unconnected-(U1-ADC_IN0-Pad2)") (class "Default")
      (node (ref "U1") (pin "2") (pinfunction "ADC_IN0_2") (pintype "bidirectional"))
    )
    (net (code "198") (name "unconnected-(U1-ADC_IN1-Pad1)") (class "Default")
      (node (ref "U1") (pin "1") (pinfunction "ADC_IN1_1") (pintype "bidirectional"))
    )
    (net (code "199") (name "unconnected-(U1-ADC_IN2-Pad4)") (class "Default")
      (node (ref "U1") (pin "4") (pinfunction "ADC_IN2_4") (pintype "bidirectional"))
    )
    (net (code "200") (name "unconnected-(U1-ADC_IN3-Pad3)") (class "Default")
      (node (ref "U1") (pin "3") (pinfunction "ADC_IN3_3") (pintype "bidirectional"))
    )
    (net (code "201") (name "unconnected-(U1-ADC_IN4-Pad6)") (class "Default")
      (node (ref "U1") (pin "6") (pinfunction "ADC_IN4_6") (pintype "bidirectional"))
    )
    (net (code "202") (name "unconnected-(U1-ADC_IN7-Pad5)") (class "Default")
      (node (ref "U1") (pin "5") (pinfunction "ADC_IN7_5") (pintype "bidirectional"))
    )
    (net (code "203") (name "unconnected-(U1-AGND-Pad8)") (class "Default")
      (node (ref "U1") (pin "8") (pinfunction "AGND_8") (pintype "bidirectional"))
    )
    (net (code "204") (name "unconnected-(U1-CAN1_RX-Pad20)") (class "Default")
      (node (ref "U1") (pin "20") (pinfunction "CAN1_RX_20") (pintype "bidirectional"))
    )
    (net (code "205") (name "unconnected-(U1-CAN1_TX-Pad22)") (class "Default")
      (node (ref "U1") (pin "22") (pinfunction "CAN1_TX_22") (pintype "bidirectional"))
    )
    (net (code "206") (name "unconnected-(U1-ERX_JM-Pad44)") (class "Default")
      (node (ref "U1") (pin "44") (pinfunction "ERX_JM_44") (pintype "bidirectional"))
    )
    (net (code "207") (name "unconnected-(U1-ERX_JP-Pad43)") (class "Default")
      (node (ref "U1") (pin "43") (pinfunction "ERX_JP_43") (pintype "bidirectional"))
    )
    (net (code "208") (name "unconnected-(U1-ETX_JM-Pad46)") (class "Default")
      (node (ref "U1") (pin "46") (pinfunction "ETX_JM_46") (pintype "bidirectional"))
    )
    (net (code "209") (name "unconnected-(U1-ETX_JP-Pad45)") (class "Default")
      (node (ref "U1") (pin "45") (pinfunction "ETX_JP_45") (pintype "bidirectional"))
    )
    (net (code "210") (name "unconnected-(U1-IRQ2-Pad50)") (class "Default")
      (node (ref "U1") (pin "50") (pinfunction "IRQ2_50") (pintype "bidirectional"))
    )
    (net (code "211") (name "unconnected-(U1-IRQ3-Pad49)") (class "Default")
      (node (ref "U1") (pin "49") (pinfunction "IRQ3_49") (pintype "bidirectional"))
    )
    (net (code "212") (name "unconnected-(U1-IRQ7-Pad9)") (class "Default")
      (node (ref "U1") (pin "9") (pinfunction "IRQ7_9") (pintype "bidirectional"))
    )
    (net (code "213") (name "unconnected-(U1-LINKLED-Pad42)") (class "Default")
      (node (ref "U1") (pin "42") (pinfunction "LINKLED_42") (pintype "bidirectional"))
    )
    (net (code "214") (name "unconnected-(U1-OW_DAT-Pad12)") (class "Default")
      (node (ref "U1") (pin "12") (pinfunction "OW_DAT_12") (pintype "bidirectional"))
    )
    (net (code "215") (name "unconnected-(U1-RSTI-Pad11)") (class "Default")
      (node (ref "U1") (pin "11") (pinfunction "RSTI_11") (pintype "bidirectional"))
    )
    (net (code "216") (name "unconnected-(U1-SDHC_DAT3-Pad15)") (class "Default")
      (node (ref "U1") (pin "15") (pinfunction "SDHC_DAT3_15") (pintype "bidirectional"))
    )
    (net (code "217") (name "unconnected-(U1-SPEEDLED-Pad40)") (class "Default")
      (node (ref "U1") (pin "40") (pinfunction "SPEEDLED_40") (pintype "bidirectional"))
    )
    (net (code "218") (name "unconnected-(U1-T0IN-Pad19)") (class "Default")
      (node (ref "U1") (pin "19") (pinfunction "T0IN_19") (pintype "bidirectional"))
    )
    (net (code "219") (name "unconnected-(U1-T1IN-Pad21)") (class "Default")
      (node (ref "U1") (pin "21") (pinfunction "T1IN_21") (pintype "bidirectional"))
    )
    (net (code "220") (name "unconnected-(U1-T3IN-Pad25)") (class "Default")
      (node (ref "U1") (pin "25") (pinfunction "T3IN_25") (pintype "bidirectional"))
    )
    (net (code "221") (name "unconnected-(U1-UART0_CTS-Pad30)") (class "Default")
      (node (ref "U1") (pin "30") (pinfunction "UART0_CTS_30") (pintype "bidirectional"))
    )
    (net (code "222") (name "unconnected-(U1-UART0_RTS-Pad28)") (class "Default")
      (node (ref "U1") (pin "28") (pinfunction "UART0_RTS_28") (pintype "bidirectional"))
    )
    (net (code "223") (name "unconnected-(U1-UART0_RX-Pad24)") (class "Default")
      (node (ref "U1") (pin "24") (pinfunction "UART0_RX_24") (pintype "bidirectional"))
    )
    (net (code "224") (name "unconnected-(U1-UART0_TX-Pad26)") (class "Default")
      (node (ref "U1") (pin "26") (pinfunction "UART0_TX_26") (pintype "bidirectional"))
    )
    (net (code "225") (name "unconnected-(U1-UART2_CTS-Pad10)") (class "Default")
      (node (ref "U1") (pin "10") (pinfunction "UART2_CTS_10") (pintype "bidirectional"))
    )
    (net (code "226") (name "unconnected-(U1-UART2_RTS-Pad14)") (class "Default")
      (node (ref "U1") (pin "14") (pinfunction "UART2_RTS_14") (pintype "bidirectional"))
    )
    (net (code "227") (name "unconnected-(U1-UART2_RX-Pad13)") (class "Default")
      (node (ref "U1") (pin "13") (pinfunction "UART2_RX_13") (pintype "bidirectional"))
    )
    (net (code "228") (name "unconnected-(U1-UART2_TX-Pad16)") (class "Default")
      (node (ref "U1") (pin "16") (pinfunction "UART2_TX_16") (pintype "bidirectional"))
    )
    (net (code "229") (name "unconnected-(U1-USBO_DM-Pad51)") (class "Default")
      (node (ref "U1") (pin "51") (pinfunction "USBO_DM_51") (pintype "bidirectional"))
    )
    (net (code "230") (name "unconnected-(U1-USBO_DP-Pad52)") (class "Default")
      (node (ref "U1") (pin "52") (pinfunction "USBO_DP_52") (pintype "bidirectional"))
    )
    (net (code "231") (name "unconnected-(U1-VCC3VE-Pad41)") (class "Default")
      (node (ref "U1") (pin "41") (pinfunction "VCC3VE_41") (pintype "bidirectional"))
    )
    (net (code "232") (name "unconnected-(U1-VDDA_DAC_ADC-Pad7)") (class "Default")
      (node (ref "U1") (pin "7") (pinfunction "VDDA_DAC_ADC_7") (pintype "bidirectional"))
    )
    (net (code "233") (name "unconnected-(U2-COMP-PadB7)") (class "Default")
      (node (ref "U2") (pin "B7") (pinfunction "COMP_B7") (pintype "bidirectional"))
    )
    (net (code "234") (name "unconnected-(U2-EXTV_CC-PadF6)") (class "Default")
      (node (ref "U2") (pin "F6") (pinfunction "EXTV_CC_F6") (pintype "bidirectional"))
    )
    (net (code "235") (name "unconnected-(U2-PLLIN-PadB9)") (class "Default")
      (node (ref "U2") (pin "B9") (pinfunction "PLLIN_B9") (pintype "bidirectional"))
    )
    (net (code "236") (name "unconnected-(U2-SS-PadA6)") (class "Default")
      (node (ref "U2") (pin "A6") (pinfunction "SS_A6") (pintype "bidirectional"))
    )
    (net (code "237") (name "unconnected-(U2-STBYMD-PadA10)") (class "Default")
      (node (ref "U2") (pin "A10") (pinfunction "STBYMD_A10") (pintype "bidirectional"))
    )
    (net (code "238") (name "unconnected-(U3-TIMER1-Pad2)") (class "Default")
      (node (ref "U3") (pin "2") (pinfunction "TIMER1_2") (pintype "bidirectional"))
    )
    (net (code "239") (name "unconnected-(U3-TIMER2-Pad4)") (class "Default")
      (node (ref "U3") (pin "4") (pinfunction "TIMER2_4") (pintype "bidirectional"))
    )
    (net (code "240") (name "unconnected-(U3-TIMER3-Pad6)") (class "Default")
      (node (ref "U3") (pin "6") (pinfunction "TIMER3_6") (pintype "bidirectional"))
    )
    (net (code "241") (name "unconnected-(U3-TIMER4-Pad8)") (class "Default")
      (node (ref "U3") (pin "8") (pinfunction "TIMER4_8") (pintype "bidirectional"))
    )
    (net (code "242") (name "unconnected-(U4-TIMER1-Pad2)") (class "Default")
      (node (ref "U4") (pin "2") (pinfunction "TIMER1_2") (pintype "bidirectional"))
    )
    (net (code "243") (name "unconnected-(U4-TIMER2-Pad4)") (class "Default")
      (node (ref "U4") (pin "4") (pinfunction "TIMER2_4") (pintype "bidirectional"))
    )
    (net (code "244") (name "unconnected-(U4-TIMER3-Pad6)") (class "Default")
      (node (ref "U4") (pin "6") (pinfunction "TIMER3_6") (pintype "bidirectional"))
    )
    (net (code "245") (name "unconnected-(U4-TIMER4-Pad8)") (class "Default")
      (node (ref "U4") (pin "8") (pinfunction "TIMER4_8") (pintype "bidirectional"))
    )
  )
)
